# STLINK-V3EC.net
KiCad netlist of a schematic drawn in Altium Designer
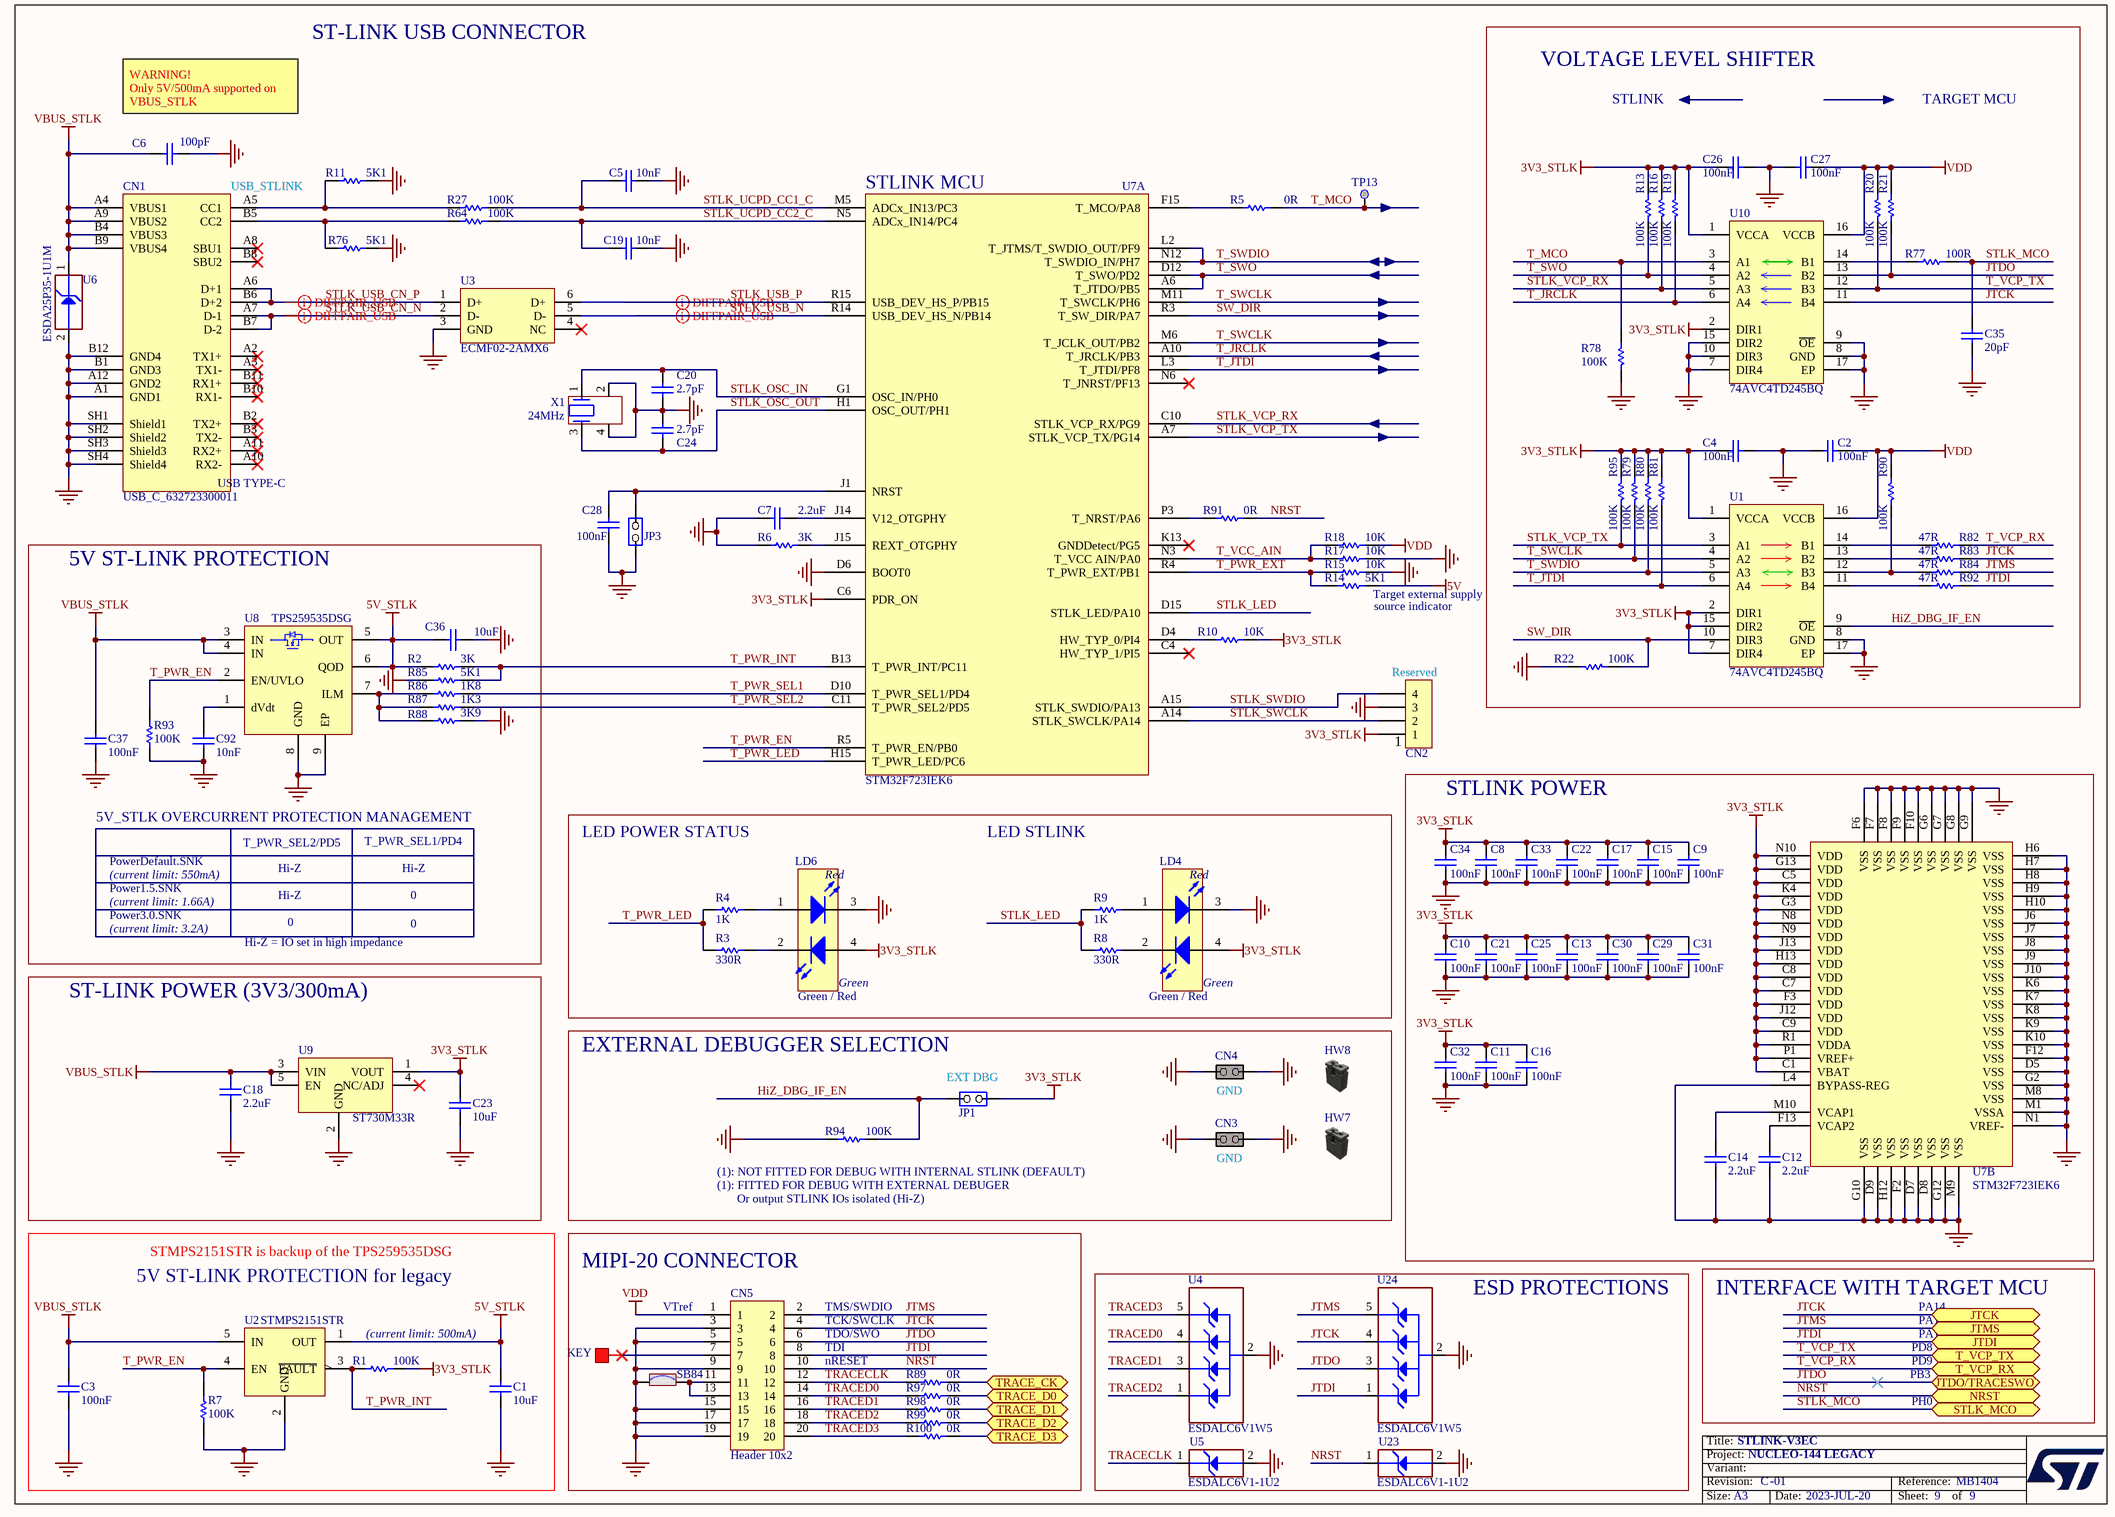
[diagram p0: STLINK-V3EC.SchDoc]

(export (version "E")
  (design (tool "Eeschema 10.0.6"))
  (components
    (comp (ref "C1")
      (value "10uF")
      (footprint "MCD_PARTS:C0603")
      (description "Capacitor, MLCC, 10uF, 10V, X5R, +/-10%, 0603, T=0.8mm")
      (fields (field (name "INTERNAL_PART_NUMBER") "MCD-00099") (field (name "MANUFACTURER") "MURATA"))
      (libsource (lib "MCD_PARTS_database") (part "Capacitor"))
    )
    (comp (ref "C2")
      (value "100nF")
      (footprint "MCD_PARTS:C0402")
      (description "Capacitor, MLCC, 100nF, 16V, X7R, 10%, 0402, T=0.5mm")
      (fields
        (field (name "INTERNAL_PART_NUMBER") "MCD-00006")
        (field (name "MANUFACTURER_PART_NUMBER") "CC0402KRX7R7BB104")
        (field (name "PROVIDED_BY") "SUBCO")
      )
      (libsource (lib "MCD_PARTS_database") (part "Capacitor"))
    )
    (comp (ref "C3")
      (value "100nF")
      (footprint "MCD_PARTS:C0402")
      (description "Capacitor, MLCC, 100nF, 25V, X7R, +/-10%, 0402, T=0.5mm")
      (fields (field (name "INTERNAL_PART_NUMBER") "MCD-02355") (field (name "MANUFACTURER") "WALSIN"))
      (libsource (lib "MCD_PARTS_database") (part "Capacitor"))
    )
    (comp (ref "C4")
      (value "100nF")
      (footprint "MCD_PARTS:C0402")
      (description "Capacitor, MLCC, 100nF, 16V, X7R, 10%, 0402, T=0.5mm")
      (fields
        (field (name "INTERNAL_PART_NUMBER") "MCD-00006")
        (field (name "MANUFACTURER_PART_NUMBER") "CC0402KRX7R7BB104")
        (field (name "PROVIDED_BY") "SUBCO")
      )
      (libsource (lib "MCD_PARTS_database") (part "Capacitor"))
    )
    (comp (ref "C5")
      (value "10nF")
      (footprint "MCD_PARTS:C0402")
      (description "Capacitor, MLCC, 10nF, 50V, X7R, +/-10%, 0402, T=0.5mm")
      (fields (field (name "INTERNAL_PART_NUMBER") "MCD-02198") (field (name "MANUFACTURER") "YAGEO"))
      (libsource (lib "MCD_PARTS_database") (part "Capacitor"))
    )
    (comp (ref "C6")
      (value "100pF")
      (footprint "MCD_PARTS:C0402")
      (description "Capacitor, MLCC, 100pF, 50V, NPO, +/-5%, 0402, T=0.5mm")
      (fields (field (name "INTERNAL_PART_NUMBER") "MCD-00205") (field (name "MANUFACTURER") "YAGEO"))
      (libsource (lib "MCD_PARTS_database") (part "Capacitor"))
    )
    (comp (ref "C7")
      (value "2.2uF")
      (footprint "MCD_PARTS:C0402")
      (description "Capacitor, MLCC, 2.2uF, 6.3V, X5R, +/-10%, 0402, T=0.5mm")
      (fields (field (name "INTERNAL_PART_NUMBER") "MCD-02606") (field (name "MANUFACTURER") "YAGEO"))
      (libsource (lib "MCD_PARTS_database") (part "Capacitor"))
    )
    (comp (ref "C8")
      (value "100nF")
      (footprint "MCD_PARTS:C0402")
      (description "Capacitor, MLCC, 100nF, 16V, X7R, 10%, 0402, T=0.5mm")
      (fields
        (field (name "INTERNAL_PART_NUMBER") "MCD-00006")
        (field (name "MANUFACTURER_PART_NUMBER") "CC0402KRX7R7BB104")
        (field (name "PROVIDED_BY") "SUBCO")
      )
      (libsource (lib "MCD_PARTS_database") (part "Capacitor"))
    )
    (comp (ref "C9")
      (value "100nF")
      (footprint "MCD_PARTS:C0402")
      (description "Capacitor, MLCC, 100nF, 16V, X7R, 10%, 0402, T=0.5mm")
      (fields
        (field (name "INTERNAL_PART_NUMBER") "MCD-00006")
        (field (name "MANUFACTURER_PART_NUMBER") "CC0402KRX7R7BB104")
        (field (name "PROVIDED_BY") "SUBCO")
      )
      (libsource (lib "MCD_PARTS_database") (part "Capacitor"))
    )
    (comp (ref "C10")
      (value "100nF")
      (footprint "MCD_PARTS:C0402")
      (description "Capacitor, MLCC, 100nF, 16V, X7R, 10%, 0402, T=0.5mm")
      (fields
        (field (name "INTERNAL_PART_NUMBER") "MCD-00006")
        (field (name "MANUFACTURER_PART_NUMBER") "CC0402KRX7R7BB104")
        (field (name "PROVIDED_BY") "SUBCO")
      )
      (libsource (lib "MCD_PARTS_database") (part "Capacitor"))
    )
    (comp (ref "C11")
      (value "100nF")
      (footprint "MCD_PARTS:C0402")
      (description "Capacitor, MLCC, 100nF, 16V, X7R, 10%, 0402, T=0.5mm")
      (fields
        (field (name "INTERNAL_PART_NUMBER") "MCD-00006")
        (field (name "MANUFACTURER_PART_NUMBER") "CC0402KRX7R7BB104")
        (field (name "PROVIDED_BY") "SUBCO")
      )
      (libsource (lib "MCD_PARTS_database") (part "Capacitor"))
    )
    (comp (ref "C12")
      (value "2.2uF")
      (footprint "MCD_PARTS:C0402")
      (description "Capacitor, MLCC, 2.2uF, 6.3V, X5R, +/-10%, 0402, T=0.5mm")
      (fields (field (name "INTERNAL_PART_NUMBER") "MCD-02606") (field (name "MANUFACTURER") "YAGEO"))
      (libsource (lib "MCD_PARTS_database") (part "Capacitor"))
    )
    (comp (ref "C13")
      (value "100nF")
      (footprint "MCD_PARTS:C0402")
      (description "Capacitor, MLCC, 100nF, 16V, X7R, 10%, 0402, T=0.5mm")
      (fields
        (field (name "INTERNAL_PART_NUMBER") "MCD-00006")
        (field (name "MANUFACTURER_PART_NUMBER") "CC0402KRX7R7BB104")
        (field (name "PROVIDED_BY") "SUBCO")
      )
      (libsource (lib "MCD_PARTS_database") (part "Capacitor"))
    )
    (comp (ref "C14")
      (value "2.2uF")
      (footprint "MCD_PARTS:C0402")
      (description "Capacitor, MLCC, 2.2uF, 6.3V, X5R, +/-10%, 0402, T=0.5mm")
      (fields (field (name "INTERNAL_PART_NUMBER") "MCD-02606") (field (name "MANUFACTURER") "YAGEO"))
      (libsource (lib "MCD_PARTS_database") (part "Capacitor"))
    )
    (comp (ref "C15")
      (value "100nF")
      (footprint "MCD_PARTS:C0402")
      (description "Capacitor, MLCC, 100nF, 16V, X7R, 10%, 0402, T=0.5mm")
      (fields
        (field (name "INTERNAL_PART_NUMBER") "MCD-00006")
        (field (name "MANUFACTURER_PART_NUMBER") "CC0402KRX7R7BB104")
        (field (name "PROVIDED_BY") "SUBCO")
      )
      (libsource (lib "MCD_PARTS_database") (part "Capacitor"))
    )
    (comp (ref "C16")
      (value "100nF")
      (footprint "MCD_PARTS:C0402")
      (description "Capacitor, MLCC, 100nF, 16V, X7R, 10%, 0402, T=0.5mm")
      (fields
        (field (name "INTERNAL_PART_NUMBER") "MCD-00006")
        (field (name "MANUFACTURER_PART_NUMBER") "CC0402KRX7R7BB104")
        (field (name "PROVIDED_BY") "SUBCO")
      )
      (libsource (lib "MCD_PARTS_database") (part "Capacitor"))
    )
    (comp (ref "C17")
      (value "100nF")
      (footprint "MCD_PARTS:C0402")
      (description "Capacitor, MLCC, 100nF, 16V, X7R, 10%, 0402, T=0.5mm")
      (fields
        (field (name "INTERNAL_PART_NUMBER") "MCD-00006")
        (field (name "MANUFACTURER_PART_NUMBER") "CC0402KRX7R7BB104")
        (field (name "PROVIDED_BY") "SUBCO")
      )
      (libsource (lib "MCD_PARTS_database") (part "Capacitor"))
    )
    (comp (ref "C18")
      (value "2.2uF")
      (footprint "MCD_PARTS:C0805")
      (description "Capacitor, MLCC, 2.2uF, 25V, X7R, +/-10%, 0805, T=1,25mm")
      (fields
        (field (name "INTERNAL_PART_NUMBER") "MCD-02372")
        (field (name "MANUFACTURER_PART_NUMBER") "GRM21BR71E225KE11L")
        (field (name "PROVIDED_BY") "SUBCO")
      )
      (libsource (lib "MCD_PARTS_database") (part "Capacitor"))
    )
    (comp (ref "C19")
      (value "10nF")
      (footprint "MCD_PARTS:C0402")
      (description "Capacitor, MLCC, 10nF, 50V, X7R, +/-10%, 0402, T=0.5mm")
      (fields (field (name "INTERNAL_PART_NUMBER") "MCD-02198") (field (name "MANUFACTURER") "YAGEO"))
      (libsource (lib "MCD_PARTS_database") (part "Capacitor"))
    )
    (comp (ref "C20")
      (value "2.7pF")
      (footprint "MCD_PARTS:C0402")
      (description "Capacitor, MLCC, 2.7pF, 50V, NPO, +/-0.1pF, 0402, T=0.5mm")
      (fields (field (name "INTERNAL_PART_NUMBER") "MCD-01774") (field (name "MANUFACTURER") "YAGEO"))
      (libsource (lib "MCD_PARTS_database") (part "Capacitor"))
    )
    (comp (ref "C21")
      (value "100nF")
      (footprint "MCD_PARTS:C0402")
      (description "Capacitor, MLCC, 100nF, 16V, X7R, 10%, 0402, T=0.5mm")
      (fields
        (field (name "INTERNAL_PART_NUMBER") "MCD-00006")
        (field (name "MANUFACTURER_PART_NUMBER") "CC0402KRX7R7BB104")
        (field (name "PROVIDED_BY") "SUBCO")
      )
      (libsource (lib "MCD_PARTS_database") (part "Capacitor"))
    )
    (comp (ref "C22")
      (value "100nF")
      (footprint "MCD_PARTS:C0402")
      (description "Capacitor, MLCC, 100nF, 16V, X7R, 10%, 0402, T=0.5mm")
      (fields
        (field (name "INTERNAL_PART_NUMBER") "MCD-00006")
        (field (name "MANUFACTURER_PART_NUMBER") "CC0402KRX7R7BB104")
        (field (name "PROVIDED_BY") "SUBCO")
      )
      (libsource (lib "MCD_PARTS_database") (part "Capacitor"))
    )
    (comp (ref "C23")
      (value "10uF")
      (footprint "MCD_PARTS:C0603")
      (description "Capacitor, MLCC, 10uF, 10V, X5R, +/-10%, 0603, T=0.8mm")
      (fields (field (name "INTERNAL_PART_NUMBER") "MCD-00099") (field (name "MANUFACTURER") "MURATA"))
      (libsource (lib "MCD_PARTS_database") (part "Capacitor"))
    )
    (comp (ref "C24")
      (value "2.7pF")
      (footprint "MCD_PARTS:C0402")
      (description "Capacitor, MLCC, 2.7pF, 50V, NPO, +/-0.1pF, 0402, T=0.5mm")
      (fields (field (name "INTERNAL_PART_NUMBER") "MCD-01774") (field (name "MANUFACTURER") "YAGEO"))
      (libsource (lib "MCD_PARTS_database") (part "Capacitor"))
    )
    (comp (ref "C25")
      (value "100nF")
      (footprint "MCD_PARTS:C0402")
      (description "Capacitor, MLCC, 100nF, 16V, X7R, 10%, 0402, T=0.5mm")
      (fields
        (field (name "INTERNAL_PART_NUMBER") "MCD-00006")
        (field (name "MANUFACTURER_PART_NUMBER") "CC0402KRX7R7BB104")
        (field (name "PROVIDED_BY") "SUBCO")
      )
      (libsource (lib "MCD_PARTS_database") (part "Capacitor"))
    )
    (comp (ref "C26")
      (value "100nF")
      (footprint "MCD_PARTS:C0402")
      (description "Capacitor, MLCC, 100nF, 16V, X7R, 10%, 0402, T=0.5mm")
      (fields
        (field (name "INTERNAL_PART_NUMBER") "MCD-00006")
        (field (name "MANUFACTURER_PART_NUMBER") "CC0402KRX7R7BB104")
        (field (name "PROVIDED_BY") "SUBCO")
      )
      (libsource (lib "MCD_PARTS_database") (part "Capacitor"))
    )
    (comp (ref "C27")
      (value "100nF")
      (footprint "MCD_PARTS:C0402")
      (description "Capacitor, MLCC, 100nF, 16V, X7R, 10%, 0402, T=0.5mm")
      (fields
        (field (name "INTERNAL_PART_NUMBER") "MCD-00006")
        (field (name "MANUFACTURER_PART_NUMBER") "CC0402KRX7R7BB104")
        (field (name "PROVIDED_BY") "SUBCO")
      )
      (libsource (lib "MCD_PARTS_database") (part "Capacitor"))
    )
    (comp (ref "C28")
      (value "100nF")
      (footprint "MCD_PARTS:C0402")
      (description "Capacitor, MLCC, 100nF, 16V, X7R, 10%, 0402, T=0.5mm")
      (fields
        (field (name "INTERNAL_PART_NUMBER") "MCD-00006")
        (field (name "MANUFACTURER_PART_NUMBER") "CC0402KRX7R7BB104")
        (field (name "PROVIDED_BY") "SUBCO")
      )
      (libsource (lib "MCD_PARTS_database") (part "Capacitor"))
    )
    (comp (ref "C29")
      (value "100nF")
      (footprint "MCD_PARTS:C0402")
      (description "Capacitor, MLCC, 100nF, 16V, X7R, 10%, 0402, T=0.5mm")
      (fields
        (field (name "INTERNAL_PART_NUMBER") "MCD-00006")
        (field (name "MANUFACTURER_PART_NUMBER") "CC0402KRX7R7BB104")
        (field (name "PROVIDED_BY") "SUBCO")
      )
      (libsource (lib "MCD_PARTS_database") (part "Capacitor"))
    )
    (comp (ref "C30")
      (value "100nF")
      (footprint "MCD_PARTS:C0402")
      (description "Capacitor, MLCC, 100nF, 16V, X7R, 10%, 0402, T=0.5mm")
      (fields
        (field (name "INTERNAL_PART_NUMBER") "MCD-00006")
        (field (name "MANUFACTURER_PART_NUMBER") "CC0402KRX7R7BB104")
        (field (name "PROVIDED_BY") "SUBCO")
      )
      (libsource (lib "MCD_PARTS_database") (part "Capacitor"))
    )
    (comp (ref "C31")
      (value "100nF")
      (footprint "MCD_PARTS:C0402")
      (description "Capacitor, MLCC, 100nF, 16V, X7R, 10%, 0402, T=0.5mm")
      (fields
        (field (name "INTERNAL_PART_NUMBER") "MCD-00006")
        (field (name "MANUFACTURER_PART_NUMBER") "CC0402KRX7R7BB104")
        (field (name "PROVIDED_BY") "SUBCO")
      )
      (libsource (lib "MCD_PARTS_database") (part "Capacitor"))
    )
    (comp (ref "C32")
      (value "100nF")
      (footprint "MCD_PARTS:C0402")
      (description "Capacitor, MLCC, 100nF, 16V, X7R, 10%, 0402, T=0.5mm")
      (fields
        (field (name "INTERNAL_PART_NUMBER") "MCD-00006")
        (field (name "MANUFACTURER_PART_NUMBER") "CC0402KRX7R7BB104")
        (field (name "PROVIDED_BY") "SUBCO")
      )
      (libsource (lib "MCD_PARTS_database") (part "Capacitor"))
    )
    (comp (ref "C33")
      (value "100nF")
      (footprint "MCD_PARTS:C0402")
      (description "Capacitor, MLCC, 100nF, 16V, X7R, 10%, 0402, T=0.5mm")
      (fields
        (field (name "INTERNAL_PART_NUMBER") "MCD-00006")
        (field (name "MANUFACTURER_PART_NUMBER") "CC0402KRX7R7BB104")
        (field (name "PROVIDED_BY") "SUBCO")
      )
      (libsource (lib "MCD_PARTS_database") (part "Capacitor"))
    )
    (comp (ref "C34")
      (value "100nF")
      (footprint "MCD_PARTS:C0402")
      (description "Capacitor, MLCC, 100nF, 16V, X7R, 10%, 0402, T=0.5mm")
      (fields
        (field (name "INTERNAL_PART_NUMBER") "MCD-00006")
        (field (name "MANUFACTURER_PART_NUMBER") "CC0402KRX7R7BB104")
        (field (name "PROVIDED_BY") "SUBCO")
      )
      (libsource (lib "MCD_PARTS_database") (part "Capacitor"))
    )
    (comp (ref "C35")
      (value "20pF")
      (footprint "MCD_PARTS:C0402")
      (description "Capacitor, MLCC, 20pF, 50V, NPO, 5%, 0402, T=0,5mm")
      (fields
        (field (name "INTERNAL_PART_NUMBER") "MCD-00016")
        (field (name "MANUFACTURER_PART_NUMBER") "CC0402JRNPO9BN200")
        (field (name "PROVIDED_BY") "SUBCO")
      )
      (libsource (lib "MCD_PARTS_database") (part "Capacitor"))
    )
    (comp (ref "C36")
      (value "10uF")
      (footprint "MCD_PARTS:C0603")
      (description "Capacitor, MLCC, 10uF, 10V, X5R, +/-10%, 0603, T=0.8mm")
      (fields (field (name "INTERNAL_PART_NUMBER") "MCD-00099") (field (name "MANUFACTURER") "MURATA"))
      (libsource (lib "MCD_PARTS_database") (part "Capacitor"))
    )
    (comp (ref "C37")
      (value "100nF")
      (footprint "MCD_PARTS:C0402")
      (description "Capacitor, MLCC, 100nF, 25V, X7R, +/-10%, 0402, T=0.5mm")
      (fields (field (name "INTERNAL_PART_NUMBER") "MCD-02355") (field (name "MANUFACTURER") "WALSIN"))
      (libsource (lib "MCD_PARTS_database") (part "Capacitor"))
    )
    (comp (ref "C92")
      (value "10nF")
      (footprint "MCD_PARTS:C0402")
      (description "Capacitor, MLCC, 10nF, 50V, X7R, +/-10%, 0402, T=0.5mm")
      (fields (field (name "INTERNAL_PART_NUMBER") "MCD-02198") (field (name "MANUFACTURER") "YAGEO"))
      (libsource (lib "MCD_PARTS_database") (part "Capacitor"))
    )
    (comp (ref "CN1")
      (value "USB_C_632723300011")
      (footprint "MCD_PARTS:CON_USB-TYPEC_WE_632723300011")
      (description "Connector_USB_TypeC, 24pins, RA, TH, T=1.9mm (USB certified)")
      (fields
        (field (name "INTERNAL_PART_NUMBER") "MCD-02273")
        (field (name "MANUFACTURER") "WURTH ELEKTRONIK")
      )
      (libsource (lib "MCD_PARTS_database") (part "USB_TYPE_C_Receptacle"))
    )
    (comp (ref "CN2")
      (value "Header 4x1")
      (footprint "MCD_PARTS:CON_SAMTEC_TSW-104-07-G-S")
      (description "Header, 4x1, 2,54mm, VR, TH, Height 5.84mm/2.54mm")
      (fields
        (field (name "INTERNAL_PART_NUMBER") "MCD-00029")
        (field (name "MANUFACTURER_PART_NUMBER") "TSW-104-07-x-S")
        (field (name "PROVIDED_BY") "SUBCO")
      )
      (libsource (lib "MCD_PARTS_database") (part "Header 4x1"))
    )
    (comp (ref "CN3")
      (value "Jumper_Header 2x1")
      (footprint "MCD_PARTS:CON_SAMTEC_TSW-102-09-X-S")
      (description "Header, 2x1, 2,54mm, VR, TH, Height 5.84mm/10.16mm")
      (fields
        (field (name "INTERNAL_PART_NUMBER") "MCD-00214")
        (field (name "MANUFACTURER_PART_NUMBER") "TSW-102-09-x-S")
        (field (name "PROVIDED_BY") "SUBCO")
      )
      (libsource (lib "MCD_PARTS_database") (part "Jumper_Header 2x1"))
    )
    (comp (ref "CN4")
      (value "Jumper_Header 2x1")
      (footprint "MCD_PARTS:CON_SAMTEC_TSW-102-09-X-S")
      (description "Header, 2x1, 2,54mm, VR, TH, Height 5.84mm/10.16mm")
      (fields
        (field (name "INTERNAL_PART_NUMBER") "MCD-00214")
        (field (name "MANUFACTURER_PART_NUMBER") "TSW-102-09-x-S")
        (field (name "PROVIDED_BY") "SUBCO")
      )
      (libsource (lib "MCD_PARTS_database") (part "Jumper_Header 2x1"))
    )
    (comp (ref "CN5")
      (value "Header 10x2")
      (footprint "MCD_PARTS:CON_SAMTEC_FTSH-110-01-L-DV")
      (description "Header, 10x2, 1.27mm, VR, SMD, T=3.05mm")
      (fields (field (name "INTERNAL_PART_NUMBER") "MCD-00557") (field (name "BMS_PART_NUMBER") "9183690"))
      (libsource (lib "MCD_PARTS_database") (part "Header 10x2"))
    )
    (comp (ref "HW7")
      (value "Shunt Black 2.54mm")
      (description "SHUNT 2.54mm BLACK")
      (fields
        (field (name "INTERNAL_PART_NUMBER") "MCD-00043")
        (field (name "MANUFACTURER_PART_NUMBER") "SNT-100-BK-G")
        (field (name "PROVIDED_BY") "SUBCO")
      )
      (libsource (lib "MCD_PARTS_database") (part "Shunt Black 2.54mm"))
    )
    (comp (ref "HW8")
      (value "Shunt Black 2.54mm")
      (description "SHUNT 2.54mm BLACK")
      (fields
        (field (name "INTERNAL_PART_NUMBER") "MCD-00043")
        (field (name "MANUFACTURER_PART_NUMBER") "SNT-100-BK-G")
        (field (name "PROVIDED_BY") "SUBCO")
      )
      (libsource (lib "MCD_PARTS_database") (part "Shunt Black 2.54mm"))
    )
    (comp (ref "JP1")
      (value "Jumper_Header 2x1")
      (footprint "MCD_PARTS:CON_SAMTEC_TSW-102-07-G-S")
      (description "Header, 2x1, 2,54mm, VR, TH, Height 5.84mm/2.54mm")
      (fields (field (name "INTERNAL_PART_NUMBER") "MCD-00045") (field (name "MANUFACTURER") "SAMTEC"))
      (libsource (lib "MCD_PARTS_database") (part "Jumper_Header 2x1"))
    )
    (comp (ref "JP3")
      (value "Jumper_Header 2x1")
      (footprint "MCD_PARTS:CON_SAMTEC_TSW-102-07-G-S")
      (description "Header, 2x1, 2,54mm, VR, TH, Height 5.84mm/2.54mm")
      (fields (field (name "INTERNAL_PART_NUMBER") "MCD-00045") (field (name "MANUFACTURER") "SAMTEC"))
      (libsource (lib "MCD_PARTS_database") (part "Jumper_Header 2x1"))
    )
    (comp (ref "LD4")
      (value "Green / Red")
      (footprint "MCD_PARTS:LED_BI-GR_WE-150141SV73110")
      (description "LED Bicolor, Green/Red, 2V, 20mA,  4-PLCC")
      (fields
        (field (name "INTERNAL_PART_NUMBER") "MCD-02631")
        (field (name "MANUFACTURER") "WURTH ELEKTRONIK")
      )
      (libsource (lib "MCD_PARTS_database") (part "LED_BICOLOR"))
    )
    (comp (ref "LD6")
      (value "Green / Red")
      (footprint "MCD_PARTS:LED_BI-GR_WE-150141SV73110")
      (description "LED Bicolor, Green/Red, 2V, 20mA,  4-PLCC")
      (fields
        (field (name "INTERNAL_PART_NUMBER") "MCD-02631")
        (field (name "MANUFACTURER") "WURTH ELEKTRONIK")
      )
      (libsource (lib "MCD_PARTS_database") (part "LED_BICOLOR"))
    )
    (comp (ref "R1")
      (value "100K")
      (footprint "MCD_PARTS:R0402")
      (description "Resistor,100K,0402,1%,1/16W")
      (fields
        (field (name "INTERNAL_PART_NUMBER") "MCD-00059")
        (field (name "MANUFACTURER_PART_NUMBER") "RC0402FR-07100KL")
        (field (name "PROVIDED_BY") "SUBCO")
      )
      (libsource (lib "MCD_PARTS_database") (part "Resistor"))
    )
    (comp (ref "R2")
      (value "3K")
      (footprint "MCD_PARTS:R0402")
      (description "Resistor, 3K, 0402, +/-1%, 1/16W")
      (fields (field (name "INTERNAL_PART_NUMBER") "MCD-00185") (field (name "MANUFACTURER") "YAGEO"))
      (libsource (lib "MCD_PARTS_database") (part "Resistor"))
    )
    (comp (ref "R3")
      (value "330R")
      (footprint "MCD_PARTS:R0402")
      (description "Resistor, 330R, 0402, +/-1%, 1/16W")
      (fields (field (name "INTERNAL_PART_NUMBER") "MCD-00062") (field (name "MANUFACTURER") "YAGEO"))
      (libsource (lib "MCD_PARTS_database") (part "Resistor"))
    )
    (comp (ref "R4")
      (value "1K")
      (footprint "MCD_PARTS:R0402")
      (description "Resistor, 1K, 0402, +/-0.1%, 1/16W, +/-25ppm/°C")
      (fields (field (name "INTERNAL_PART_NUMBER") "MCD-02665") (field (name "MANUFACTURER") "YAGEO"))
      (libsource (lib "MCD_PARTS_database") (part "Resistor"))
    )
    (comp (ref "R5")
      (value "0R")
      (footprint "MCD_PARTS:R0402")
      (description "Resistor, 0R, 0402, +/-5%, 1/16W")
      (fields (field (name "INTERNAL_PART_NUMBER") "MCD-00052") (field (name "MANUFACTURER") "YAGEO"))
      (libsource (lib "MCD_PARTS_database") (part "Resistor"))
    )
    (comp (ref "R6")
      (value "3K")
      (footprint "MCD_PARTS:R0402")
      (description "Resistor,3K,0402,1%,1/16W")
      (fields
        (field (name "INTERNAL_PART_NUMBER") "MCD-00185")
        (field (name "MANUFACTURER_PART_NUMBER") "RC0402FR-073KL")
        (field (name "PROVIDED_BY") "SUBCO")
      )
      (libsource (lib "MCD_PARTS_database") (part "Resistor"))
    )
    (comp (ref "R7")
      (value "100K")
      (footprint "MCD_PARTS:R0402")
      (description "Resistor,100K,0402,1%,1/16W")
      (fields
        (field (name "INTERNAL_PART_NUMBER") "MCD-00059")
        (field (name "MANUFACTURER_PART_NUMBER") "RC0402FR-07100KL")
        (field (name "PROVIDED_BY") "SUBCO")
      )
      (libsource (lib "MCD_PARTS_database") (part "Resistor"))
    )
    (comp (ref "R8")
      (value "330R")
      (footprint "MCD_PARTS:R0402")
      (description "Resistor, 330R, 0402, +/-1%, 1/16W")
      (fields (field (name "INTERNAL_PART_NUMBER") "MCD-00062") (field (name "MANUFACTURER") "YAGEO"))
      (libsource (lib "MCD_PARTS_database") (part "Resistor"))
    )
    (comp (ref "R9")
      (value "1K")
      (footprint "MCD_PARTS:R0402")
      (description "Resistor, 1K, 0402, +/-0.1%, 1/16W, +/-25ppm/°C")
      (fields (field (name "INTERNAL_PART_NUMBER") "MCD-02665") (field (name "MANUFACTURER") "YAGEO"))
      (libsource (lib "MCD_PARTS_database") (part "Resistor"))
    )
    (comp (ref "R10")
      (value "10K")
      (footprint "MCD_PARTS:R0402")
      (description "Resistor,10K,0402,1%,1/16W")
      (fields
        (field (name "INTERNAL_PART_NUMBER") "MCD-00053")
        (field (name "MANUFACTURER_PART_NUMBER") "RC0402FR-0710KL")
        (field (name "PROVIDED_BY") "SUBCO")
      )
      (libsource (lib "MCD_PARTS_database") (part "Resistor"))
    )
    (comp (ref "R11")
      (value "5K1")
      (footprint "MCD_PARTS:R0402")
      (description "Resistor, 5K1, 0402, +/-1%, 1/16W")
      (fields (field (name "INTERNAL_PART_NUMBER") "MCD-00333") (field (name "MANUFACTURER") "YAGEO"))
      (libsource (lib "MCD_PARTS_database") (part "Resistor"))
    )
    (comp (ref "R13")
      (value "100K")
      (footprint "MCD_PARTS:R0402")
      (description "Resistor,100K,0402,1%,1/16W")
      (fields
        (field (name "INTERNAL_PART_NUMBER") "MCD-00059")
        (field (name "MANUFACTURER_PART_NUMBER") "RC0402FR-07100KL")
        (field (name "PROVIDED_BY") "Subcon")
      )
      (libsource (lib "MCD_PARTS_database") (part "Resistor"))
    )
    (comp (ref "R14")
      (value "5K1")
      (footprint "MCD_PARTS:R0402")
      (description "Resistor, 5K1, 0402, +/-1%, 1/16W")
      (fields (field (name "INTERNAL_PART_NUMBER") "MCD-00333") (field (name "MANUFACTURER") "YAGEO"))
      (libsource (lib "MCD_PARTS_database") (part "Resistor"))
    )
    (comp (ref "R15")
      (value "10K")
      (footprint "MCD_PARTS:R0402")
      (description "Resistor, 10K, 0402, +/-1%, 1/16W")
      (fields (field (name "INTERNAL_PART_NUMBER") "MCD-00053") (field (name "BMS_PART_NUMBER") "9131590"))
      (libsource (lib "MCD_PARTS_database") (part "Resistor"))
    )
    (comp (ref "R16")
      (value "100K")
      (footprint "MCD_PARTS:R0402")
      (description "Resistor,100K,0402,1%,1/16W")
      (fields
        (field (name "INTERNAL_PART_NUMBER") "MCD-00059")
        (field (name "MANUFACTURER_PART_NUMBER") "RC0402FR-07100KL")
        (field (name "PROVIDED_BY") "Subcon")
      )
      (libsource (lib "MCD_PARTS_database") (part "Resistor"))
    )
    (comp (ref "R17")
      (value "10K")
      (footprint "MCD_PARTS:R0402")
      (description "Resistor, 10K, 0402, +/-1%, 1/16W")
      (fields (field (name "INTERNAL_PART_NUMBER") "MCD-00053") (field (name "BMS_PART_NUMBER") "9131590"))
      (libsource (lib "MCD_PARTS_database") (part "Resistor"))
    )
    (comp (ref "R18")
      (value "10K")
      (footprint "MCD_PARTS:R0402")
      (description "Resistor, 10K, 0402, +/-1%, 1/16W")
      (fields (field (name "INTERNAL_PART_NUMBER") "MCD-00053") (field (name "BMS_PART_NUMBER") "9131590"))
      (libsource (lib "MCD_PARTS_database") (part "Resistor"))
    )
    (comp (ref "R19")
      (value "100K")
      (footprint "MCD_PARTS:R0402")
      (description "Resistor,100K,0402,1%,1/16W")
      (fields
        (field (name "INTERNAL_PART_NUMBER") "MCD-00059")
        (field (name "MANUFACTURER_PART_NUMBER") "RC0402FR-07100KL")
        (field (name "PROVIDED_BY") "Subcon")
      )
      (libsource (lib "MCD_PARTS_database") (part "Resistor"))
    )
    (comp (ref "R20")
      (value "100K")
      (footprint "MCD_PARTS:R0402")
      (description "Resistor,100K,0402,1%,1/16W")
      (fields
        (field (name "INTERNAL_PART_NUMBER") "MCD-00059")
        (field (name "MANUFACTURER_PART_NUMBER") "RC0402FR-07100KL")
        (field (name "PROVIDED_BY") "Subcon")
      )
      (libsource (lib "MCD_PARTS_database") (part "Resistor"))
    )
    (comp (ref "R21")
      (value "100K")
      (footprint "MCD_PARTS:R0402")
      (description "Resistor,100K,0402,1%,1/16W")
      (fields
        (field (name "INTERNAL_PART_NUMBER") "MCD-00059")
        (field (name "MANUFACTURER_PART_NUMBER") "RC0402FR-07100KL")
        (field (name "PROVIDED_BY") "Subcon")
      )
      (libsource (lib "MCD_PARTS_database") (part "Resistor"))
    )
    (comp (ref "R22")
      (value "100K")
      (footprint "MCD_PARTS:R0402")
      (description "Resistor,100K,0402,1%,1/16W")
      (fields
        (field (name "INTERNAL_PART_NUMBER") "MCD-00059")
        (field (name "MANUFACTURER_PART_NUMBER") "RC0402FR-07100KL")
        (field (name "PROVIDED_BY") "Subcon")
      )
      (libsource (lib "MCD_PARTS_database") (part "Resistor"))
    )
    (comp (ref "R27")
      (value "100K")
      (footprint "MCD_PARTS:R0402")
      (description "Resistor, 100K, 0402, +/-1%, 1/16W")
      (fields (field (name "INTERNAL_PART_NUMBER") "MCD-00059") (field (name "MANUFACTURER") "YAGEO"))
      (libsource (lib "MCD_PARTS_database") (part "Resistor"))
    )
    (comp (ref "R64")
      (value "100K")
      (footprint "MCD_PARTS:R0402")
      (description "Resistor, 100K, 0402, +/-1%, 1/16W")
      (fields (field (name "INTERNAL_PART_NUMBER") "MCD-00059") (field (name "MANUFACTURER") "YAGEO"))
      (libsource (lib "MCD_PARTS_database") (part "Resistor"))
    )
    (comp (ref "R76")
      (value "5K1")
      (footprint "MCD_PARTS:R0402")
      (description "Resistor, 5K1, 0402, +/-1%, 1/16W")
      (fields (field (name "INTERNAL_PART_NUMBER") "MCD-00333") (field (name "MANUFACTURER") "YAGEO"))
      (libsource (lib "MCD_PARTS_database") (part "Resistor"))
    )
    (comp (ref "R77")
      (value "100R")
      (footprint "MCD_PARTS:R0402")
      (description "Resistor, 100R, 0402, +/- 1%, 1/16W")
      (fields (field (name "INTERNAL_PART_NUMBER") "MCD-00067") (field (name "MANUFACTURER") "YAGEO"))
      (libsource (lib "MCD_PARTS_database") (part "Resistor"))
    )
    (comp (ref "R78")
      (value "100K")
      (footprint "MCD_PARTS:R0402")
      (description "Resistor,100K,0402,1%,1/16W")
      (fields
        (field (name "INTERNAL_PART_NUMBER") "MCD-00059")
        (field (name "MANUFACTURER_PART_NUMBER") "RC0402FR-07100KL")
        (field (name "PROVIDED_BY") "Subcon")
      )
      (libsource (lib "MCD_PARTS_database") (part "Resistor"))
    )
    (comp (ref "R79")
      (value "100K")
      (footprint "MCD_PARTS:R0402")
      (description "Resistor,100K,0402,1%,1/16W")
      (fields
        (field (name "INTERNAL_PART_NUMBER") "MCD-00059")
        (field (name "MANUFACTURER_PART_NUMBER") "RC0402FR-07100KL")
        (field (name "PROVIDED_BY") "Subcon")
      )
      (libsource (lib "MCD_PARTS_database") (part "Resistor"))
    )
    (comp (ref "R80")
      (value "100K")
      (footprint "MCD_PARTS:R0402")
      (description "Resistor,100K,0402,1%,1/16W")
      (fields
        (field (name "INTERNAL_PART_NUMBER") "MCD-00059")
        (field (name "MANUFACTURER_PART_NUMBER") "RC0402FR-07100KL")
        (field (name "PROVIDED_BY") "Subcon")
      )
      (libsource (lib "MCD_PARTS_database") (part "Resistor"))
    )
    (comp (ref "R81")
      (value "100K")
      (footprint "MCD_PARTS:R0402")
      (description "Resistor,100K,0402,1%,1/16W")
      (fields
        (field (name "INTERNAL_PART_NUMBER") "MCD-00059")
        (field (name "MANUFACTURER_PART_NUMBER") "RC0402FR-07100KL")
        (field (name "PROVIDED_BY") "Subcon")
      )
      (libsource (lib "MCD_PARTS_database") (part "Resistor"))
    )
    (comp (ref "R82")
      (value "47R")
      (footprint "MCD_PARTS:R0402")
      (description "Resistor,47R,0402,1%,1/16W")
      (fields
        (field (name "INTERNAL_PART_NUMBER") "MCD-00481")
        (field (name "MANUFACTURER_PART_NUMBER") "RC0402FR-0747RL")
        (field (name "PROVIDED_BY") "SUBCO")
      )
      (libsource (lib "MCD_PARTS_database") (part "Resistor"))
    )
    (comp (ref "R83")
      (value "47R")
      (footprint "MCD_PARTS:R0402")
      (description "Resistor,47R,0402,1%,1/16W")
      (fields
        (field (name "INTERNAL_PART_NUMBER") "MCD-00481")
        (field (name "MANUFACTURER_PART_NUMBER") "RC0402FR-0747RL")
        (field (name "PROVIDED_BY") "SUBCO")
      )
      (libsource (lib "MCD_PARTS_database") (part "Resistor"))
    )
    (comp (ref "R84")
      (value "47R")
      (footprint "MCD_PARTS:R0402")
      (description "Resistor,47R,0402,1%,1/16W")
      (fields
        (field (name "INTERNAL_PART_NUMBER") "MCD-00481")
        (field (name "MANUFACTURER_PART_NUMBER") "RC0402FR-0747RL")
        (field (name "PROVIDED_BY") "SUBCO")
      )
      (libsource (lib "MCD_PARTS_database") (part "Resistor"))
    )
    (comp (ref "R85")
      (value "5K1")
      (footprint "MCD_PARTS:R0402")
      (description "Resistor, 5K1, 0402, +/-1%, 1/16W")
      (fields (field (name "INTERNAL_PART_NUMBER") "MCD-00333") (field (name "MANUFACTURER") "YAGEO"))
      (libsource (lib "MCD_PARTS_database") (part "Resistor"))
    )
    (comp (ref "R86")
      (value "1K8")
      (footprint "MCD_PARTS:R0402")
      (description "Resistor, 1K8, 0402, +/-1%, 1/16W")
      (fields (field (name "INTERNAL_PART_NUMBER") "MCD-00409") (field (name "MANUFACTURER") "YAGEO"))
      (libsource (lib "MCD_PARTS_database") (part "Resistor"))
    )
    (comp (ref "R87")
      (value "1K3")
      (footprint "MCD_PARTS:R0402")
      (description "Resistor, 1K3, 0402, +/-1%, 1/16W")
      (fields (field (name "INTERNAL_PART_NUMBER") "MCD-00381") (field (name "MANUFACTURER") "YAGEO"))
      (libsource (lib "MCD_PARTS_database") (part "Resistor"))
    )
    (comp (ref "R88")
      (value "3K9")
      (footprint "MCD_PARTS:R0402")
      (description "Resistor, 3K9, 0402, +/-1%, 1/16W, +/-100ppm/°C")
      (fields (field (name "INTERNAL_PART_NUMBER") "MCD-02455") (field (name "MANUFACTURER") "YAGEO"))
      (libsource (lib "MCD_PARTS_database") (part "Resistor"))
    )
    (comp (ref "R89")
      (value "0R")
      (footprint "MCD_PARTS:R0402")
      (description "Resistor,0R,0402,5%,1/16W")
      (fields
        (field (name "INTERNAL_PART_NUMBER") "MCD-00052")
        (field (name "MANUFACTURER_PART_NUMBER") "RC0402JR-070RL")
        (field (name "PROVIDED_BY") "SUBCO")
      )
      (libsource (lib "MCD_PARTS_database") (part "Resistor"))
    )
    (comp (ref "R90")
      (value "100K")
      (footprint "MCD_PARTS:R0402")
      (description "Resistor,100K,0402,1%,1/16W")
      (fields
        (field (name "INTERNAL_PART_NUMBER") "MCD-00059")
        (field (name "MANUFACTURER_PART_NUMBER") "RC0402FR-07100KL")
        (field (name "PROVIDED_BY") "Subcon")
      )
      (libsource (lib "MCD_PARTS_database") (part "Resistor"))
    )
    (comp (ref "R91")
      (value "0R")
      (footprint "MCD_PARTS:R0402")
      (description "Resistor, 0R, 0402, +/-5%, 1/16W")
      (fields (field (name "INTERNAL_PART_NUMBER") "MCD-00052") (field (name "MANUFACTURER") "YAGEO"))
      (libsource (lib "MCD_PARTS_database") (part "Resistor"))
    )
    (comp (ref "R92")
      (value "47R")
      (footprint "MCD_PARTS:R0402")
      (description "Resistor,47R,0402,1%,1/16W")
      (fields
        (field (name "INTERNAL_PART_NUMBER") "MCD-00481")
        (field (name "MANUFACTURER_PART_NUMBER") "RC0402FR-0747RL")
        (field (name "PROVIDED_BY") "SUBCO")
      )
      (libsource (lib "MCD_PARTS_database") (part "Resistor"))
    )
    (comp (ref "R93")
      (value "100K")
      (footprint "MCD_PARTS:R0402")
      (description "Resistor, 100K, 0402, +/-1%, 1/16W")
      (fields (field (name "INTERNAL_PART_NUMBER") "MCD-00059") (field (name "MANUFACTURER") "YAGEO"))
      (libsource (lib "MCD_PARTS_database") (part "Resistor"))
    )
    (comp (ref "R94")
      (value "100K")
      (footprint "MCD_PARTS:R0402")
      (description "Resistor, 100K, 0402, +/-1%, 1/16W")
      (fields (field (name "INTERNAL_PART_NUMBER") "MCD-00059") (field (name "MANUFACTURER") "YAGEO"))
      (libsource (lib "MCD_PARTS_database") (part "Resistor"))
    )
    (comp (ref "R95")
      (value "100K")
      (footprint "MCD_PARTS:R0402")
      (description "Resistor,100K,0402,1%,1/16W")
      (fields
        (field (name "INTERNAL_PART_NUMBER") "MCD-00059")
        (field (name "MANUFACTURER_PART_NUMBER") "RC0402FR-07100KL")
        (field (name "PROVIDED_BY") "Subcon")
      )
      (libsource (lib "MCD_PARTS_database") (part "Resistor"))
    )
    (comp (ref "R97")
      (value "0R")
      (footprint "MCD_PARTS:R0402")
      (description "Resistor,0R,0402,5%,1/16W")
      (fields
        (field (name "INTERNAL_PART_NUMBER") "MCD-00052")
        (field (name "MANUFACTURER_PART_NUMBER") "RC0402JR-070RL")
        (field (name "PROVIDED_BY") "SUBCO")
      )
      (libsource (lib "MCD_PARTS_database") (part "Resistor"))
    )
    (comp (ref "R98")
      (value "0R")
      (footprint "MCD_PARTS:R0402")
      (description "Resistor,0R,0402,5%,1/16W")
      (fields
        (field (name "INTERNAL_PART_NUMBER") "MCD-00052")
        (field (name "MANUFACTURER_PART_NUMBER") "RC0402JR-070RL")
        (field (name "PROVIDED_BY") "SUBCO")
      )
      (libsource (lib "MCD_PARTS_database") (part "Resistor"))
    )
    (comp (ref "R99")
      (value "0R")
      (footprint "MCD_PARTS:R0402")
      (description "Resistor,0R,0402,5%,1/16W")
      (fields
        (field (name "INTERNAL_PART_NUMBER") "MCD-00052")
        (field (name "MANUFACTURER_PART_NUMBER") "RC0402JR-070RL")
        (field (name "PROVIDED_BY") "SUBCO")
      )
      (libsource (lib "MCD_PARTS_database") (part "Resistor"))
    )
    (comp (ref "R100")
      (value "0R")
      (footprint "MCD_PARTS:R0402")
      (description "Resistor,0R,0402,5%,1/16W")
      (fields
        (field (name "INTERNAL_PART_NUMBER") "MCD-00052")
        (field (name "MANUFACTURER_PART_NUMBER") "RC0402JR-070RL")
        (field (name "PROVIDED_BY") "SUBCO")
      )
      (libsource (lib "MCD_PARTS_database") (part "Resistor"))
    )
    (comp (ref "SB84")
      (value "SB_ON")
      (footprint "MCD_PARTS:SOLDER-BRIDGE_R0402-0R")
      (description "Solder Bridge 0402 ON")
      (fields
        (field (name "INTERNAL_PART_NUMBER") "MCD-01618")
        (field (name "MANUFACTURER_PART_NUMBER") "RC0402JR-070RL")
        (field (name "PROVIDED_BY") "SUBCO")
      )
      (libsource (lib "MCD_PARTS_database") (part "SB_ON"))
    )
    (comp (ref "TP13")
      (value "Test Point")
      (footprint "MCD_PARTS:TP_SMD_1MM")
      (description "Test Point 1mm")
      (fields
        (field (name "INTERNAL_PART_NUMBER") "MCD-00074")
        (field (name "MANUFACTURER_PART_NUMBER") "n/a")
      )
      (libsource (lib "MCD_PARTS_database") (part "Test Point"))
    )
    (comp (ref "U1")
      (value "74AVC4TD245BQ")
      (footprint "MCD_PARTS:ICC_DHVQFN16-EPAD_SOT763-1_2P5X3P5_H0P85_P050")
      (description "4-bit dual supply translating transceiver with configurable voltage translation; 3-state")
      (fields
        (field (name "INTERNAL_PART_NUMBER") "MCD-01945")
        (field (name "MANUFACTURER_PART_NUMBER") "74AVC4TD245BQ,115")
      )
      (libsource (lib "MCD_PARTS_database") (part "74AVC4TD245BQ"))
    )
    (comp (ref "U2")
      (value "STMPS2151STR")
      (footprint "MCD_PARTS:MOS_SOT23-5L")
      (description "500mA, Enhanced single channel power switches with active high enable pin")
      (fields
        (field (name "INTERNAL_PART_NUMBER") "MCD-00159")
        (field (name "MANUFACTURER") "STMICROELECTRONICS")
        (field (name "PROVIDED_BY") "Subcon")
      )
      (libsource (lib "MCD_PARTS_database") (part "STMPS2151STR"))
    )
    (comp (ref "U3")
      (value "ECMF02-2AMX6")
      (footprint "MCD_PARTS:ESD_QFN-6L_1P7X1P5_P050")
      (description "Common mode filter with ESD protection for USB 2.0 interface")
      (fields (field (name "INTERNAL_PART_NUMBER") "MCD-00649") (field (name "BMS_PART_NUMBER") "9151138"))
      (libsource (lib "MCD_PARTS_database") (part "ECMF02-2AMX6"))
    )
    (comp (ref "U4")
      (value "ESDALC6V1W5")
      (footprint "MCD_PARTS:ESD_SOT323-5L")
      (description "Dual Transil array for ESD protection")
      (fields (field (name "INTERNAL_PART_NUMBER") "MCD-00136") (field (name "BMS_PART_NUMBER") "9151112"))
      (libsource (lib "MCD_PARTS_database") (part "ESDALC6V1W5"))
    )
    (comp (ref "U5")
      (value "ESDALC6V1-1U2")
      (footprint "MCD_PARTS:ESD_ST0201")
      (description "ESD protection 6V1")
      (fields (field (name "INTERNAL_PART_NUMBER") "MCD-00170") (field (name "BMS_PART_NUMBER") "9151132"))
      (libsource (lib "") (part "ESD-TRANSIL_1"))
    )
    (comp (ref "U6")
      (value "ESDA25P35-1U1M")
      (footprint "MCD_PARTS:ESD_QFN1610_2N_1K_2A")
      (description "High power Transient voltage suppressor:25V/35A EOS and ESD transients protection.")
      (fields
        (field (name "INTERNAL_PART_NUMBER") "MCD-01207")
        (field (name "MANUFACTURER") "STMICROELECTRONICS")
        (field (name "PROVIDED_BY") "SUBCO with ST control")
      )
      (libsource (lib "MCD_PARTS_database") (part "ESD-TRANSIL"))
    )
    (comp (ref "U7")
      (value "STM32F723IEK6")
      (footprint "MCD_PARTS:ICC_UFBGA201_176+25_10X10_P065")
      (description "MCU, Arm Cortex-M7 32-bit MCU, 512KB Flash, 276KB RAM, With Crypto")
      (fields (field (name "INTERNAL_PART_NUMBER") "MCD-02706") (field (name "BMS_PART_NUMBER") "9175300"))
      (libsource (lib "MCD_PARTS_database") (part "STLINK-V3EC"))
    )
    (comp (ref "U8")
      (value "TPS259535DSG")
      (footprint "MCD_PARTS:ICC_WSON8-EPAD_2X2_P050")
      (description "eFuse with Fast Overvoltage Protection 2.7V to 18V 4A 34mOhm 8-Pin WSON")
      (fields
        (field (name "INTERNAL_PART_NUMBER") "MCD-02532")
        (field (name "MANUFACTURER") "TEXAS INSTRUMENTS")
      )
      (libsource (lib "MCD_PARTS_database") (part "TPS259535DSG"))
    )
    (comp (ref "U9")
      (value "ST730M33R")
      (footprint "MCD_PARTS:ICC_SOT23-5L_H1P45")
      (description "LDO, 3.3V, 300mA, High input voltage: 2.5V to 28V, SOT23-5L")
      (fields
        (field (name "INTERNAL_PART_NUMBER") "MCD-02514")
        (field (name "MANUFACTURER") "STMICROELECTRONICS")
      )
      (libsource (lib "MCD_PARTS_database") (part "ST730M33R"))
    )
    (comp (ref "U10")
      (value "74AVC4TD245BQ")
      (footprint "MCD_PARTS:ICC_DHVQFN16-EPAD_SOT763-1_2P5X3P5_H0P85_P050")
      (description "4-bit dual supply translating transceiver with configurable voltage translation; 3-state")
      (fields
        (field (name "INTERNAL_PART_NUMBER") "MCD-01945")
        (field (name "MANUFACTURER_PART_NUMBER") "74AVC4TD245BQ,115")
      )
      (libsource (lib "MCD_PARTS_database") (part "74AVC4TD245BQ"))
    )
    (comp (ref "U23")
      (value "ESDALC6V1-1U2")
      (footprint "MCD_PARTS:ESD_ST0201")
      (description "ESD protection 6V1")
      (fields (field (name "INTERNAL_PART_NUMBER") "MCD-00170") (field (name "BMS_PART_NUMBER") "9151132"))
      (libsource (lib "") (part "ESD-TRANSIL_1"))
    )
    (comp (ref "U24")
      (value "ESDALC6V1W5")
      (footprint "MCD_PARTS:ESD_SOT323-5L")
      (description "Dual Transil array for ESD protection")
      (fields (field (name "INTERNAL_PART_NUMBER") "MCD-00136") (field (name "BMS_PART_NUMBER") "9151112"))
      (libsource (lib "MCD_PARTS_database") (part "ESDALC6V1W5"))
    )
    (comp (ref "X1")
      (value "24MHz")
      (footprint "MCD_PARTS:CRY_NX2016SA_4P")
      (description "Crystal, 24MHz, 6pF, +/-20ppm, 80R, 2x1.6mm")
      (fields (field (name "INTERNAL_PART_NUMBER") "MCD-01036") (field (name "BMS_PART_NUMBER") "9157045"))
      (libsource (lib "MCD_PARTS_database") (part "XTAL_4_PINS"))
    )
  )
  (nets
    (net (code "1") (name "/HiZ_DBG_IF_EN") (class "Default")
      (node (ref "JP1") (pin "2") (pinfunction "NO_2") (pintype "passive"))
      (node (ref "R94") (pin "2") (pinfunction "2_2") (pintype "passive"))
      (node (ref "U1") (pin "9") (pinfunction "~{OE}_9") (pintype "passive"))
    )
    (net (code "2") (name "/JTCK") (class "Default")
      (node (ref "CN5") (pin "4") (pinfunction "4_4") (pintype "passive"))
      (node (ref "R83") (pin "2") (pinfunction "2_2") (pintype "passive"))
      (node (ref "U10") (pin "11") (pinfunction "B4_11") (pintype "passive"))
      (node (ref "U24") (pin "4") (pinfunction "IO3_4") (pintype "passive"))
    )
    (net (code "3") (name "/JTDI") (class "Default")
      (node (ref "CN5") (pin "8") (pinfunction "8_8") (pintype "passive"))
      (node (ref "R92") (pin "2") (pinfunction "2_2") (pintype "passive"))
      (node (ref "U24") (pin "1") (pinfunction "IO1_1") (pintype "passive"))
    )
    (net (code "4") (name "/JTDO") (class "Default")
      (node (ref "CN5") (pin "6") (pinfunction "6_6") (pintype "passive"))
      (node (ref "R21") (pin "1") (pinfunction "1_1") (pintype "passive"))
      (node (ref "U10") (pin "13") (pinfunction "B2_13") (pintype "passive"))
      (node (ref "U24") (pin "3") (pinfunction "IO2_3") (pintype "passive"))
    )
    (net (code "5") (name "/JTMS") (class "Default")
      (node (ref "CN5") (pin "2") (pinfunction "2_2") (pintype "passive"))
      (node (ref "R84") (pin "2") (pinfunction "2_2") (pintype "passive"))
      (node (ref "U24") (pin "5") (pinfunction "IO4_5") (pintype "passive"))
    )
    (net (code "6") (name "/NRST") (class "Default")
      (node (ref "CN5") (pin "10") (pinfunction "10_10") (pintype "passive"))
      (node (ref "R91") (pin "2") (pinfunction "2_2") (pintype "passive"))
      (node (ref "U23") (pin "1") (pinfunction "IO1_1") (pintype "passive"))
    )
    (net (code "7") (name "/STLK_LED") (class "Default")
      (node (ref "R8") (pin "1") (pinfunction "1_1") (pintype "passive"))
      (node (ref "R9") (pin "2") (pinfunction "2_2") (pintype "passive"))
      (node (ref "U7") (pin "D15") (pinfunction "STLK_LED/PA10_D15") (pintype "passive"))
    )
    (net (code "8") (name "/STLK_MCO") (class "Default")
      (node (ref "C35") (pin "1") (pinfunction "1_1") (pintype "passive"))
      (node (ref "R77") (pin "2") (pinfunction "2_2") (pintype "passive"))
    )
    (net (code "9") (name "/STLK_OSC_IN") (class "Default")
      (node (ref "C20") (pin "2") (pinfunction "2_2") (pintype "passive"))
      (node (ref "U7") (pin "G1") (pinfunction "OSC_IN/PH0_G1") (pintype "passive"))
      (node (ref "X1") (pin "1") (pinfunction "1_1") (pintype "passive"))
    )
    (net (code "10") (name "/STLK_OSC_OUT") (class "Default")
      (node (ref "C24") (pin "2") (pinfunction "2_2") (pintype "passive"))
      (node (ref "U7") (pin "H1") (pinfunction "OSC_OUT/PH1_H1") (pintype "passive"))
      (node (ref "X1") (pin "3") (pinfunction "3_3") (pintype "passive"))
    )
    (net (code "11") (name "/STLK_SWCLK") (class "Default")
      (node (ref "CN2") (pin "2") (pinfunction "2_2") (pintype "passive"))
      (node (ref "U7") (pin "A14") (pinfunction "STLK_SWCLK/PA14_A14") (pintype "passive"))
    )
    (net (code "12") (name "/STLK_SWDIO") (class "Default")
      (node (ref "CN2") (pin "4") (pinfunction "4_4") (pintype "passive"))
      (node (ref "U7") (pin "A15") (pinfunction "STLK_SWDIO/PA13_A15") (pintype "passive"))
    )
    (net (code "13") (name "/STLK_UCPD_CC1_C") (class "Default")
      (node (ref "C5") (pin "1") (pinfunction "1_1") (pintype "passive"))
      (node (ref "R27") (pin "2") (pinfunction "2_2") (pintype "passive"))
      (node (ref "U7") (pin "M5") (pinfunction "ADCx_IN13/PC3_M5") (pintype "passive"))
    )
    (net (code "14") (name "/STLK_UCPD_CC2_C") (class "Default")
      (node (ref "C19") (pin "1") (pinfunction "1_1") (pintype "passive"))
      (node (ref "R64") (pin "2") (pinfunction "2_2") (pintype "passive"))
      (node (ref "U7") (pin "N5") (pinfunction "ADCx_IN14/PC4_N5") (pintype "passive"))
    )
    (net (code "15") (name "/STLK_USB_CN_N") (class "Default")
      (node (ref "CN1") (pin "A7") (pinfunction "D-1_A7") (pintype "passive"))
      (node (ref "CN1") (pin "B7") (pinfunction "D-2_B7") (pintype "passive"))
      (node (ref "U3") (pin "2") (pinfunction "D-_2") (pintype "passive"))
    )
    (net (code "16") (name "/STLK_USB_CN_P") (class "Default")
      (node (ref "CN1") (pin "A6") (pinfunction "D+1_A6") (pintype "passive"))
      (node (ref "CN1") (pin "B6") (pinfunction "D+2_B6") (pintype "passive"))
      (node (ref "U3") (pin "1") (pinfunction "D+_1") (pintype "passive"))
    )
    (net (code "17") (name "/STLK_USB_N") (class "Default")
      (node (ref "U3") (pin "5") (pinfunction "D-_5") (pintype "passive"))
      (node (ref "U7") (pin "R14") (pinfunction "USB_DEV_HS_N/PB14_R14") (pintype "passive"))
    )
    (net (code "18") (name "/STLK_USB_P") (class "Default")
      (node (ref "U3") (pin "6") (pinfunction "D+_6") (pintype "passive"))
      (node (ref "U7") (pin "R15") (pinfunction "USB_DEV_HS_P/PB15_R15") (pintype "passive"))
    )
    (net (code "19") (name "/STLK_VCP_RX") (class "Default")
      (node (ref "R16") (pin "1") (pinfunction "1_1") (pintype "passive"))
      (node (ref "U10") (pin "5") (pinfunction "A3_5") (pintype "passive"))
      (node (ref "U7") (pin "C10") (pinfunction "STLK_VCP_RX/PG9_C10") (pintype "passive"))
    )
    (net (code "20") (name "/STLK_VCP_TX") (class "Default")
      (node (ref "R95") (pin "2") (pinfunction "2_2") (pintype "passive"))
      (node (ref "U1") (pin "3") (pinfunction "A1_3") (pintype "passive"))
      (node (ref "U7") (pin "A7") (pinfunction "STLK_VCP_TX/PG14_A7") (pintype "passive"))
    )
    (net (code "21") (name "/SW_DIR") (class "Default")
      (node (ref "R22") (pin "2") (pinfunction "2_2") (pintype "passive"))
      (node (ref "U1") (pin "10") (pinfunction "DIR3_10") (pintype "passive"))
      (node (ref "U7") (pin "R3") (pinfunction "T_SW_DIR/PA7_R3") (pintype "passive"))
    )
    (net (code "22") (name "/TRACECLK") (class "Default")
      (node (ref "CN5") (pin "12") (pinfunction "12_12") (pintype "passive"))
      (node (ref "R89") (pin "1") (pinfunction "1_1") (pintype "passive"))
      (node (ref "U5") (pin "1") (pinfunction "IO1_1") (pintype "passive"))
    )
    (net (code "23") (name "/TRACED0") (class "Default")
      (node (ref "CN5") (pin "14") (pinfunction "14_14") (pintype "passive"))
      (node (ref "R97") (pin "1") (pinfunction "1_1") (pintype "passive"))
      (node (ref "U4") (pin "4") (pinfunction "IO3_4") (pintype "passive"))
    )
    (net (code "24") (name "/TRACED1") (class "Default")
      (node (ref "CN5") (pin "16") (pinfunction "16_16") (pintype "passive"))
      (node (ref "R98") (pin "1") (pinfunction "1_1") (pintype "passive"))
      (node (ref "U4") (pin "3") (pinfunction "IO2_3") (pintype "passive"))
    )
    (net (code "25") (name "/TRACED2") (class "Default")
      (node (ref "CN5") (pin "18") (pinfunction "18_18") (pintype "passive"))
      (node (ref "R99") (pin "1") (pinfunction "1_1") (pintype "passive"))
      (node (ref "U4") (pin "1") (pinfunction "IO1_1") (pintype "passive"))
    )
    (net (code "26") (name "/TRACED3") (class "Default")
      (node (ref "CN5") (pin "20") (pinfunction "20_20") (pintype "passive"))
      (node (ref "R100") (pin "1") (pinfunction "1_1") (pintype "passive"))
      (node (ref "U4") (pin "5") (pinfunction "IO4_5") (pintype "passive"))
    )
    (net (code "27") (name "/TRACE_CK") (class "Default")
      (node (ref "R89") (pin "2") (pinfunction "2_2") (pintype "passive"))
    )
    (net (code "28") (name "/TRACE_D0") (class "Default")
      (node (ref "R97") (pin "2") (pinfunction "2_2") (pintype "passive"))
    )
    (net (code "29") (name "/TRACE_D1") (class "Default")
      (node (ref "R98") (pin "2") (pinfunction "2_2") (pintype "passive"))
    )
    (net (code "30") (name "/TRACE_D2") (class "Default")
      (node (ref "R99") (pin "2") (pinfunction "2_2") (pintype "passive"))
    )
    (net (code "31") (name "/TRACE_D3") (class "Default")
      (node (ref "R100") (pin "2") (pinfunction "2_2") (pintype "passive"))
    )
    (net (code "32") (name "/T_JRCLK") (class "Default")
      (node (ref "R19") (pin "1") (pinfunction "1_1") (pintype "passive"))
      (node (ref "U10") (pin "6") (pinfunction "A4_6") (pintype "passive"))
      (node (ref "U7") (pin "A10") (pinfunction "T_JRCLK/PB3_A10") (pintype "passive"))
    )
    (net (code "33") (name "/T_JTDI") (class "Default")
      (node (ref "R81") (pin "1") (pinfunction "1_1") (pintype "passive"))
      (node (ref "U1") (pin "6") (pinfunction "A4_6") (pintype "passive"))
      (node (ref "U7") (pin "L3") (pinfunction "T_JTDI/PF8_L3") (pintype "passive"))
    )
    (net (code "34") (name "/T_MCO") (class "Default")
      (node (ref "R5") (pin "2") (pinfunction "2_2") (pintype "passive"))
      (node (ref "R78") (pin "2") (pinfunction "2_2") (pintype "passive"))
      (node (ref "TP13") (pin "1") (pinfunction "1_1") (pintype "passive"))
      (node (ref "U10") (pin "3") (pinfunction "A1_3") (pintype "passive"))
    )
    (net (code "35") (name "/T_PWR_EN") (class "Default")
      (node (ref "R7") (pin "2") (pinfunction "2_2") (pintype "passive"))
      (node (ref "R93") (pin "2") (pinfunction "2_2") (pintype "passive"))
      (node (ref "U2") (pin "4") (pinfunction "EN_4") (pintype "passive"))
      (node (ref "U7") (pin "R5") (pinfunction "T_PWR_EN/PB0_R5") (pintype "passive"))
      (node (ref "U8") (pin "2") (pinfunction "EN/UVLO_2") (pintype "passive"))
    )
    (net (code "36") (name "/T_PWR_EXT") (class "Default")
      (node (ref "R14") (pin "1") (pinfunction "1_1") (pintype "passive"))
      (node (ref "R15") (pin "1") (pinfunction "1_1") (pintype "passive"))
      (node (ref "U7") (pin "R4") (pinfunction "T_PWR_EXT/PB1_R4") (pintype "passive"))
    )
    (net (code "37") (name "/T_PWR_INT") (class "Default")
      (node (ref "R1") (pin "2") (pinfunction "2_2") (pintype "passive"))
      (node (ref "R2") (pin "2") (pinfunction "2_2") (pintype "passive"))
      (node (ref "R85") (pin "2") (pinfunction "2_2") (pintype "passive"))
      (node (ref "U2") (pin "3") (pinfunction "~{FAULT}_3") (pintype "passive"))
      (node (ref "U7") (pin "B13") (pinfunction "T_PWR_INT/PC11_B13") (pintype "passive"))
    )
    (net (code "38") (name "/T_PWR_LED") (class "Default")
      (node (ref "R3") (pin "2") (pinfunction "2_2") (pintype "passive"))
      (node (ref "R4") (pin "2") (pinfunction "2_2") (pintype "passive"))
      (node (ref "U7") (pin "H15") (pinfunction "T_PWR_LED/PC6_H15") (pintype "passive"))
    )
    (net (code "39") (name "/T_PWR_SEL1") (class "Default")
      (node (ref "R86") (pin "2") (pinfunction "2_2") (pintype "passive"))
      (node (ref "U7") (pin "D10") (pinfunction "T_PWR_SEL1/PD4_D10") (pintype "passive"))
    )
    (net (code "40") (name "/T_PWR_SEL2") (class "Default")
      (node (ref "R87") (pin "2") (pinfunction "2_2") (pintype "passive"))
      (node (ref "U7") (pin "C11") (pinfunction "T_PWR_SEL2/PD5_C11") (pintype "passive"))
    )
    (net (code "41") (name "/T_SWCLK") (class "Default")
      (node (ref "R79") (pin "2") (pinfunction "2_2") (pintype "passive"))
      (node (ref "U1") (pin "4") (pinfunction "A2_4") (pintype "passive"))
      (node (ref "U7") (pin "M11") (pinfunction "T_SWCLK/PH6_M11") (pintype "passive"))
      (node (ref "U7") (pin "M6") (pinfunction "T_JCLK_OUT/PB2_M6") (pintype "passive"))
    )
    (net (code "42") (name "/T_SWDIO") (class "Default")
      (node (ref "R80") (pin "1") (pinfunction "1_1") (pintype "passive"))
      (node (ref "U1") (pin "5") (pinfunction "A3_5") (pintype "passive"))
      (node (ref "U7") (pin "L2") (pinfunction "T_JTMS/T_SWDIO_OUT/PF9_L2") (pintype "passive"))
      (node (ref "U7") (pin "N12") (pinfunction "T_SWDIO_IN/PH7_N12") (pintype "passive"))
    )
    (net (code "43") (name "/T_SWO") (class "Default")
      (node (ref "R13") (pin "1") (pinfunction "1_1") (pintype "passive"))
      (node (ref "U10") (pin "4") (pinfunction "A2_4") (pintype "passive"))
      (node (ref "U7") (pin "A6") (pinfunction "T_JTDO/PB5_A6") (pintype "passive"))
      (node (ref "U7") (pin "D12") (pinfunction "T_SWO/PD2_D12") (pintype "passive"))
    )
    (net (code "44") (name "/T_VCC_AIN") (class "Default")
      (node (ref "R17") (pin "1") (pinfunction "1_1") (pintype "passive"))
      (node (ref "R18") (pin "1") (pinfunction "1_1") (pintype "passive"))
      (node (ref "U7") (pin "N3") (pinfunction "T_VCC_AIN/PA0_N3") (pintype "passive"))
    )
    (net (code "45") (name "/T_VCP_RX") (class "Default")
      (node (ref "R82") (pin "2") (pinfunction "2_2") (pintype "passive"))
    )
    (net (code "46") (name "/T_VCP_TX") (class "Default")
      (node (ref "R20") (pin "1") (pinfunction "1_1") (pintype "passive"))
      (node (ref "U10") (pin "12") (pinfunction "B3_12") (pintype "passive"))
    )
    (net (code "47") (name "3V3_STLK") (class "Default")
      (node (ref "C10") (pin "1") (pinfunction "1_1") (pintype "passive"))
      (node (ref "C11") (pin "1") (pinfunction "1_1") (pintype "passive"))
      (node (ref "C13") (pin "1") (pinfunction "1_1") (pintype "passive"))
      (node (ref "C15") (pin "1") (pinfunction "1_1") (pintype "passive"))
      (node (ref "C16") (pin "1") (pinfunction "1_1") (pintype "passive"))
      (node (ref "C17") (pin "1") (pinfunction "1_1") (pintype "passive"))
      (node (ref "C21") (pin "1") (pinfunction "1_1") (pintype "passive"))
      (node (ref "C22") (pin "1") (pinfunction "1_1") (pintype "passive"))
      (node (ref "C23") (pin "2") (pinfunction "2_2") (pintype "passive"))
      (node (ref "C25") (pin "1") (pinfunction "1_1") (pintype "passive"))
      (node (ref "C26") (pin "2") (pinfunction "2_2") (pintype "passive"))
      (node (ref "C29") (pin "1") (pinfunction "1_1") (pintype "passive"))
      (node (ref "C30") (pin "1") (pinfunction "1_1") (pintype "passive"))
      (node (ref "C31") (pin "1") (pinfunction "1_1") (pintype "passive"))
      (node (ref "C32") (pin "1") (pinfunction "1_1") (pintype "passive"))
      (node (ref "C33") (pin "1") (pinfunction "1_1") (pintype "passive"))
      (node (ref "C34") (pin "1") (pinfunction "1_1") (pintype "passive"))
      (node (ref "C4") (pin "2") (pinfunction "2_2") (pintype "passive"))
      (node (ref "C8") (pin "1") (pinfunction "1_1") (pintype "passive"))
      (node (ref "C9") (pin "1") (pinfunction "1_1") (pintype "passive"))
      (node (ref "CN2") (pin "1") (pinfunction "1_1") (pintype "passive"))
      (node (ref "JP1") (pin "1") (pinfunction "COMMON_1") (pintype "passive"))
      (node (ref "LD4") (pin "4") (pinfunction "Green_anode_4") (pintype "passive"))
      (node (ref "LD6") (pin "4") (pinfunction "Green_anode_4") (pintype "passive"))
      (node (ref "R1") (pin "1") (pinfunction "1_1") (pintype "passive"))
      (node (ref "R10") (pin "2") (pinfunction "2_2") (pintype "passive"))
      (node (ref "R13") (pin "2") (pinfunction "2_2") (pintype "passive"))
      (node (ref "R16") (pin "2") (pinfunction "2_2") (pintype "passive"))
      (node (ref "R19") (pin "2") (pinfunction "2_2") (pintype "passive"))
      (node (ref "R79") (pin "1") (pinfunction "1_1") (pintype "passive"))
      (node (ref "R80") (pin "2") (pinfunction "2_2") (pintype "passive"))
      (node (ref "R81") (pin "2") (pinfunction "2_2") (pintype "passive"))
      (node (ref "R95") (pin "1") (pinfunction "1_1") (pintype "passive"))
      (node (ref "U1") (pin "1") (pinfunction "VCCA_1") (pintype "passive"))
      (node (ref "U1") (pin "15") (pinfunction "DIR2_15") (pintype "passive"))
      (node (ref "U1") (pin "2") (pinfunction "DIR1_2") (pintype "passive"))
      (node (ref "U1") (pin "7") (pinfunction "DIR4_7") (pintype "passive"))
      (node (ref "U10") (pin "1") (pinfunction "VCCA_1") (pintype "passive"))
      (node (ref "U10") (pin "2") (pinfunction "DIR1_2") (pintype "passive"))
      (node (ref "U7") (pin "C1") (pinfunction "VBAT_C1") (pintype "passive"))
      (node (ref "U7") (pin "C5") (pinfunction "VDD_C5") (pintype "passive"))
      (node (ref "U7") (pin "C6") (pinfunction "PDR_ON_C6") (pintype "passive"))
      (node (ref "U7") (pin "C7") (pinfunction "VDD_C7") (pintype "passive"))
      (node (ref "U7") (pin "C8") (pinfunction "VDD_C8") (pintype "passive"))
      (node (ref "U7") (pin "C9") (pinfunction "VDD_C9") (pintype "passive"))
      (node (ref "U7") (pin "F3") (pinfunction "VDD_F3") (pintype "passive"))
      (node (ref "U7") (pin "G13") (pinfunction "VDD_G13") (pintype "passive"))
      (node (ref "U7") (pin "G3") (pinfunction "VDD_G3") (pintype "passive"))
      (node (ref "U7") (pin "H13") (pinfunction "VDD_H13") (pintype "passive"))
      (node (ref "U7") (pin "J12") (pinfunction "VDD_J12") (pintype "passive"))
      (node (ref "U7") (pin "J13") (pinfunction "VDD_J13") (pintype "passive"))
      (node (ref "U7") (pin "K4") (pinfunction "VDD_K4") (pintype "passive"))
      (node (ref "U7") (pin "N10") (pinfunction "VDD_N10") (pintype "passive"))
      (node (ref "U7") (pin "N8") (pinfunction "VDD_N8") (pintype "passive"))
      (node (ref "U7") (pin "N9") (pinfunction "VDD_N9") (pintype "passive"))
      (node (ref "U7") (pin "P1") (pinfunction "VREF+_P1") (pintype "passive"))
      (node (ref "U7") (pin "R1") (pinfunction "VDDA_R1") (pintype "passive"))
      (node (ref "U9") (pin "1") (pinfunction "VOUT_1") (pintype "passive"))
    )
    (net (code "48") (name "5V") (class "Default")
      (node (ref "R14") (pin "2") (pinfunction "2_2") (pintype "passive"))
    )
    (net (code "49") (name "5V_STLK") (class "Default")
      (node (ref "C1") (pin "2") (pinfunction "2_2") (pintype "passive"))
      (node (ref "C36") (pin "2") (pinfunction "2_2") (pintype "passive"))
      (node (ref "R2") (pin "1") (pinfunction "1_1") (pintype "passive"))
      (node (ref "U2") (pin "1") (pinfunction "OUT_1") (pintype "passive"))
      (node (ref "U8") (pin "5") (pinfunction "OUT_5") (pintype "passive"))
      (node (ref "U8") (pin "6") (pinfunction "QOD_6") (pintype "passive"))
    )
    (net (code "50") (name "GND") (class "Default")
      (node (ref "C1") (pin "1") (pinfunction "1_1") (pintype "passive"))
      (node (ref "C10") (pin "2") (pinfunction "2_2") (pintype "passive"))
      (node (ref "C11") (pin "2") (pinfunction "2_2") (pintype "passive"))
      (node (ref "C12") (pin "1") (pinfunction "1_1") (pintype "passive"))
      (node (ref "C13") (pin "2") (pinfunction "2_2") (pintype "passive"))
      (node (ref "C14") (pin "1") (pinfunction "1_1") (pintype "passive"))
      (node (ref "C15") (pin "2") (pinfunction "2_2") (pintype "passive"))
      (node (ref "C16") (pin "2") (pinfunction "2_2") (pintype "passive"))
      (node (ref "C17") (pin "2") (pinfunction "2_2") (pintype "passive"))
      (node (ref "C18") (pin "1") (pinfunction "1_1") (pintype "passive"))
      (node (ref "C19") (pin "2") (pinfunction "2_2") (pintype "passive"))
      (node (ref "C2") (pin "2") (pinfunction "2_2") (pintype "passive"))
      (node (ref "C20") (pin "1") (pinfunction "1_1") (pintype "passive"))
      (node (ref "C21") (pin "2") (pinfunction "2_2") (pintype "passive"))
      (node (ref "C22") (pin "2") (pinfunction "2_2") (pintype "passive"))
      (node (ref "C23") (pin "1") (pinfunction "1_1") (pintype "passive"))
      (node (ref "C24") (pin "1") (pinfunction "1_1") (pintype "passive"))
      (node (ref "C25") (pin "2") (pinfunction "2_2") (pintype "passive"))
      (node (ref "C26") (pin "1") (pinfunction "1_1") (pintype "passive"))
      (node (ref "C27") (pin "2") (pinfunction "2_2") (pintype "passive"))
      (node (ref "C28") (pin "1") (pinfunction "1_1") (pintype "passive"))
      (node (ref "C29") (pin "2") (pinfunction "2_2") (pintype "passive"))
      (node (ref "C3") (pin "1") (pinfunction "1_1") (pintype "passive"))
      (node (ref "C30") (pin "2") (pinfunction "2_2") (pintype "passive"))
      (node (ref "C31") (pin "2") (pinfunction "2_2") (pintype "passive"))
      (node (ref "C32") (pin "2") (pinfunction "2_2") (pintype "passive"))
      (node (ref "C33") (pin "2") (pinfunction "2_2") (pintype "passive"))
      (node (ref "C34") (pin "2") (pinfunction "2_2") (pintype "passive"))
      (node (ref "C35") (pin "2") (pinfunction "2_2") (pintype "passive"))
      (node (ref "C36") (pin "1") (pinfunction "1_1") (pintype "passive"))
      (node (ref "C37") (pin "1") (pinfunction "1_1") (pintype "passive"))
      (node (ref "C4") (pin "1") (pinfunction "1_1") (pintype "passive"))
      (node (ref "C5") (pin "2") (pinfunction "2_2") (pintype "passive"))
      (node (ref "C6") (pin "2") (pinfunction "2_2") (pintype "passive"))
      (node (ref "C7") (pin "1") (pinfunction "1_1") (pintype "passive"))
      (node (ref "C8") (pin "2") (pinfunction "2_2") (pintype "passive"))
      (node (ref "C9") (pin "2") (pinfunction "2_2") (pintype "passive"))
      (node (ref "C92") (pin "1") (pinfunction "1_1") (pintype "passive"))
      (node (ref "CN1") (pin "A1") (pinfunction "GND1_A1") (pintype "passive"))
      (node (ref "CN1") (pin "A12") (pinfunction "GND2_A12") (pintype "passive"))
      (node (ref "CN1") (pin "B1") (pinfunction "GND3_B1") (pintype "passive"))
      (node (ref "CN1") (pin "B12") (pinfunction "GND4_B12") (pintype "passive"))
      (node (ref "CN1") (pin "SH1") (pinfunction "Shield1_SH1") (pintype "passive"))
      (node (ref "CN1") (pin "SH2") (pinfunction "Shield2_SH2") (pintype "passive"))
      (node (ref "CN1") (pin "SH3") (pinfunction "Shield3_SH3") (pintype "passive"))
      (node (ref "CN1") (pin "SH4") (pinfunction "Shield4_SH4") (pintype "passive"))
      (node (ref "CN2") (pin "3") (pinfunction "3_3") (pintype "passive"))
      (node (ref "CN3") (pin "1") (pinfunction "COMMON_1") (pintype "passive"))
      (node (ref "CN3") (pin "2") (pinfunction "NO_2") (pintype "passive"))
      (node (ref "CN4") (pin "1") (pinfunction "COMMON_1") (pintype "passive"))
      (node (ref "CN4") (pin "2") (pinfunction "NO_2") (pintype "passive"))
      (node (ref "CN5") (pin "15") (pinfunction "15_15") (pintype "passive"))
      (node (ref "CN5") (pin "17") (pinfunction "17_17") (pintype "passive"))
      (node (ref "CN5") (pin "19") (pinfunction "19_19") (pintype "passive"))
      (node (ref "CN5") (pin "3") (pinfunction "3_3") (pintype "passive"))
      (node (ref "CN5") (pin "5") (pinfunction "5_5") (pintype "passive"))
      (node (ref "CN5") (pin "9") (pinfunction "9_9") (pintype "passive"))
      (node (ref "JP3") (pin "2") (pinfunction "NO_2") (pintype "passive"))
      (node (ref "LD4") (pin "3") (pinfunction "RED_cathode_3") (pintype "passive"))
      (node (ref "LD6") (pin "3") (pinfunction "RED_cathode_3") (pintype "passive"))
      (node (ref "R11") (pin "2") (pinfunction "2_2") (pintype "passive"))
      (node (ref "R15") (pin "2") (pinfunction "2_2") (pintype "passive"))
      (node (ref "R17") (pin "2") (pinfunction "2_2") (pintype "passive"))
      (node (ref "R22") (pin "1") (pinfunction "1_1") (pintype "passive"))
      (node (ref "R6") (pin "2") (pinfunction "2_2") (pintype "passive"))
      (node (ref "R7") (pin "1") (pinfunction "1_1") (pintype "passive"))
      (node (ref "R76") (pin "2") (pinfunction "2_2") (pintype "passive"))
      (node (ref "R78") (pin "1") (pinfunction "1_1") (pintype "passive"))
      (node (ref "R85") (pin "1") (pinfunction "1_1") (pintype "passive"))
      (node (ref "R88") (pin "2") (pinfunction "2_2") (pintype "passive"))
      (node (ref "R93") (pin "1") (pinfunction "1_1") (pintype "passive"))
      (node (ref "R94") (pin "1") (pinfunction "1_1") (pintype "passive"))
      (node (ref "SB84") (pin "1") (pinfunction "1_1") (pintype "passive"))
      (node (ref "U1") (pin "17") (pinfunction "EP_17") (pintype "passive"))
      (node (ref "U1") (pin "8") (pinfunction "GND_8") (pintype "passive"))
      (node (ref "U10") (pin "10") (pinfunction "DIR3_10") (pintype "passive"))
      (node (ref "U10") (pin "15") (pinfunction "DIR2_15") (pintype "passive"))
      (node (ref "U10") (pin "17") (pinfunction "EP_17") (pintype "passive"))
      (node (ref "U10") (pin "7") (pinfunction "DIR4_7") (pintype "passive"))
      (node (ref "U10") (pin "8") (pinfunction "GND_8") (pintype "passive"))
      (node (ref "U10") (pin "9") (pinfunction "~{OE}_9") (pintype "passive"))
      (node (ref "U2") (pin "2") (pinfunction "GND_2") (pintype "passive"))
      (node (ref "U23") (pin "2") (pinfunction "GND_2") (pintype "passive"))
      (node (ref "U24") (pin "2") (pinfunction "GND_2") (pintype "passive"))
      (node (ref "U3") (pin "3") (pinfunction "GND_3") (pintype "passive"))
      (node (ref "U4") (pin "2") (pinfunction "GND_2") (pintype "passive"))
      (node (ref "U5") (pin "2") (pinfunction "GND_2") (pintype "passive"))
      (node (ref "U6") (pin "2") (pinfunction "GND_2") (pintype "passive"))
      (node (ref "U7") (pin "D5") (pinfunction "VSS_D5") (pintype "passive"))
      (node (ref "U7") (pin "D6") (pinfunction "BOOT0_D6") (pintype "passive"))
      (node (ref "U7") (pin "D7") (pinfunction "VSS_D7") (pintype "passive"))
      (node (ref "U7") (pin "D8") (pinfunction "VSS_D8") (pintype "passive"))
      (node (ref "U7") (pin "D9") (pinfunction "VSS_D9") (pintype "passive"))
      (node (ref "U7") (pin "F10") (pinfunction "VSS_F10") (pintype "passive"))
      (node (ref "U7") (pin "F12") (pinfunction "VSS_F12") (pintype "passive"))
      (node (ref "U7") (pin "F2") (pinfunction "VSS_F2") (pintype "passive"))
      (node (ref "U7") (pin "F6") (pinfunction "VSS_F6") (pintype "passive"))
      (node (ref "U7") (pin "F7") (pinfunction "VSS_F7") (pintype "passive"))
      (node (ref "U7") (pin "F8") (pinfunction "VSS_F8") (pintype "passive"))
      (node (ref "U7") (pin "F9") (pinfunction "VSS_F9") (pintype "passive"))
      (node (ref "U7") (pin "G10") (pinfunction "VSS_G10") (pintype "passive"))
      (node (ref "U7") (pin "G12") (pinfunction "VSS_G12") (pintype "passive"))
      (node (ref "U7") (pin "G2") (pinfunction "VSS_G2") (pintype "passive"))
      (node (ref "U7") (pin "G6") (pinfunction "VSS_G6") (pintype "passive"))
      (node (ref "U7") (pin "G7") (pinfunction "VSS_G7") (pintype "passive"))
      (node (ref "U7") (pin "G8") (pinfunction "VSS_G8") (pintype "passive"))
      (node (ref "U7") (pin "G9") (pinfunction "VSS_G9") (pintype "passive"))
      (node (ref "U7") (pin "H10") (pinfunction "VSS_H10") (pintype "passive"))
      (node (ref "U7") (pin "H12") (pinfunction "VSS_H12") (pintype "passive"))
      (node (ref "U7") (pin "H6") (pinfunction "VSS_H6") (pintype "passive"))
      (node (ref "U7") (pin "H7") (pinfunction "VSS_H7") (pintype "passive"))
      (node (ref "U7") (pin "H8") (pinfunction "VSS_H8") (pintype "passive"))
      (node (ref "U7") (pin "H9") (pinfunction "VSS_H9") (pintype "passive"))
      (node (ref "U7") (pin "J10") (pinfunction "VSS_J10") (pintype "passive"))
      (node (ref "U7") (pin "J6") (pinfunction "VSS_J6") (pintype "passive"))
      (node (ref "U7") (pin "J7") (pinfunction "VSS_J7") (pintype "passive"))
      (node (ref "U7") (pin "J8") (pinfunction "VSS_J8") (pintype "passive"))
      (node (ref "U7") (pin "J9") (pinfunction "VSS_J9") (pintype "passive"))
      (node (ref "U7") (pin "K10") (pinfunction "VSS_K10") (pintype "passive"))
      (node (ref "U7") (pin "K6") (pinfunction "VSS_K6") (pintype "passive"))
      (node (ref "U7") (pin "K7") (pinfunction "VSS_K7") (pintype "passive"))
      (node (ref "U7") (pin "K8") (pinfunction "VSS_K8") (pintype "passive"))
      (node (ref "U7") (pin "K9") (pinfunction "VSS_K9") (pintype "passive"))
      (node (ref "U7") (pin "L4") (pinfunction "BYPASS-REG_L4") (pintype "passive"))
      (node (ref "U7") (pin "M1") (pinfunction "VSSA_M1") (pintype "passive"))
      (node (ref "U7") (pin "M8") (pinfunction "VSS_M8") (pintype "passive"))
      (node (ref "U7") (pin "M9") (pinfunction "VSS_M9") (pintype "passive"))
      (node (ref "U7") (pin "N1") (pinfunction "VREF-_N1") (pintype "passive"))
      (node (ref "U8") (pin "8") (pinfunction "GND_8") (pintype "passive"))
      (node (ref "U8") (pin "9") (pinfunction "EP_9") (pintype "passive"))
      (node (ref "U9") (pin "2") (pinfunction "GND_2") (pintype "passive"))
      (node (ref "X1") (pin "2") (pinfunction "2_2") (pintype "passive"))
      (node (ref "X1") (pin "4") (pinfunction "4_4") (pintype "passive"))
    )
    (net (code "51") (name "Net-(CN1-CC1)") (class "Default")
      (node (ref "CN1") (pin "A5") (pinfunction "CC1_A5") (pintype "passive"))
      (node (ref "R11") (pin "1") (pinfunction "1_1") (pintype "passive"))
      (node (ref "R27") (pin "1") (pinfunction "1_1") (pintype "passive"))
    )
    (net (code "52") (name "Net-(CN1-CC2)") (class "Default")
      (node (ref "CN1") (pin "B5") (pinfunction "CC2_B5") (pintype "passive"))
      (node (ref "R64") (pin "1") (pinfunction "1_1") (pintype "passive"))
      (node (ref "R76") (pin "1") (pinfunction "1_1") (pintype "passive"))
    )
    (net (code "53") (name "Net-(CN5-Pad11)") (class "Default")
      (node (ref "CN5") (pin "11") (pinfunction "11_11") (pintype "passive"))
      (node (ref "CN5") (pin "13") (pinfunction "13_13") (pintype "passive"))
      (node (ref "SB84") (pin "2") (pinfunction "2_2") (pintype "passive"))
    )
    (net (code "54") (name "Net-(JP3-COMMON)") (class "Default")
      (node (ref "C28") (pin "2") (pinfunction "2_2") (pintype "passive"))
      (node (ref "JP3") (pin "1") (pinfunction "COMMON_1") (pintype "passive"))
      (node (ref "U7") (pin "J1") (pinfunction "NRST_J1") (pintype "passive"))
    )
    (net (code "55") (name "Net-(LD4-Green_cathode)") (class "Default")
      (node (ref "LD4") (pin "2") (pinfunction "Green_cathode_2") (pintype "passive"))
      (node (ref "R8") (pin "2") (pinfunction "2_2") (pintype "passive"))
    )
    (net (code "56") (name "Net-(LD4-Red_anode)") (class "Default")
      (node (ref "LD4") (pin "1") (pinfunction "Red_anode_1") (pintype "passive"))
      (node (ref "R9") (pin "1") (pinfunction "1_1") (pintype "passive"))
    )
    (net (code "57") (name "Net-(LD6-Green_cathode)") (class "Default")
      (node (ref "LD6") (pin "2") (pinfunction "Green_cathode_2") (pintype "passive"))
      (node (ref "R3") (pin "1") (pinfunction "1_1") (pintype "passive"))
    )
    (net (code "58") (name "Net-(LD6-Red_anode)") (class "Default")
      (node (ref "LD6") (pin "1") (pinfunction "Red_anode_1") (pintype "passive"))
      (node (ref "R4") (pin "1") (pinfunction "1_1") (pintype "passive"))
    )
    (net (code "59") (name "Net-(U1-B1)") (class "Default")
      (node (ref "R82") (pin "1") (pinfunction "1_1") (pintype "passive"))
      (node (ref "U1") (pin "14") (pinfunction "B1_14") (pintype "passive"))
    )
    (net (code "60") (name "Net-(U1-B2)") (class "Default")
      (node (ref "R83") (pin "1") (pinfunction "1_1") (pintype "passive"))
      (node (ref "U1") (pin "13") (pinfunction "B2_13") (pintype "passive"))
    )
    (net (code "61") (name "Net-(U1-B3)") (class "Default")
      (node (ref "R84") (pin "1") (pinfunction "1_1") (pintype "passive"))
      (node (ref "R90") (pin "1") (pinfunction "1_1") (pintype "passive"))
      (node (ref "U1") (pin "12") (pinfunction "B3_12") (pintype "passive"))
    )
    (net (code "62") (name "Net-(U1-B4)") (class "Default")
      (node (ref "R92") (pin "1") (pinfunction "1_1") (pintype "passive"))
      (node (ref "U1") (pin "11") (pinfunction "B4_11") (pintype "passive"))
    )
    (net (code "63") (name "Net-(U7A-HW_TYP_0{slash}PI4)") (class "Default")
      (node (ref "R10") (pin "1") (pinfunction "1_1") (pintype "passive"))
      (node (ref "U7") (pin "D4") (pinfunction "HW_TYP_0/PI4_D4") (pintype "passive"))
    )
    (net (code "64") (name "Net-(U7A-REXT_OTGPHY)") (class "Default")
      (node (ref "R6") (pin "1") (pinfunction "1_1") (pintype "passive"))
      (node (ref "U7") (pin "J15") (pinfunction "REXT_OTGPHY_J15") (pintype "passive"))
    )
    (net (code "65") (name "Net-(U7A-T_MCO{slash}PA8)") (class "Default")
      (node (ref "R5") (pin "1") (pinfunction "1_1") (pintype "passive"))
      (node (ref "U7") (pin "F15") (pinfunction "T_MCO/PA8_F15") (pintype "passive"))
    )
    (net (code "66") (name "Net-(U7A-T_NRST{slash}PA6)") (class "Default")
      (node (ref "R91") (pin "1") (pinfunction "1_1") (pintype "passive"))
      (node (ref "U7") (pin "P3") (pinfunction "T_NRST/PA6_P3") (pintype "passive"))
    )
    (net (code "67") (name "Net-(U7A-V12_OTGPHY)") (class "Default")
      (node (ref "C7") (pin "2") (pinfunction "2_2") (pintype "passive"))
      (node (ref "U7") (pin "J14") (pinfunction "V12_OTGPHY_J14") (pintype "passive"))
    )
    (net (code "68") (name "Net-(U7B-VCAP1)") (class "Default")
      (node (ref "C14") (pin "2") (pinfunction "2_2") (pintype "passive"))
      (node (ref "U7") (pin "M10") (pinfunction "VCAP1_M10") (pintype "passive"))
    )
    (net (code "69") (name "Net-(U7B-VCAP2)") (class "Default")
      (node (ref "C12") (pin "2") (pinfunction "2_2") (pintype "passive"))
      (node (ref "U7") (pin "F13") (pinfunction "VCAP2_F13") (pintype "passive"))
    )
    (net (code "70") (name "Net-(U8-ILM)") (class "Default")
      (node (ref "R86") (pin "1") (pinfunction "1_1") (pintype "passive"))
      (node (ref "R87") (pin "1") (pinfunction "1_1") (pintype "passive"))
      (node (ref "R88") (pin "1") (pinfunction "1_1") (pintype "passive"))
      (node (ref "U8") (pin "7") (pinfunction "ILM_7") (pintype "passive"))
    )
    (net (code "71") (name "Net-(U8-dVdt)") (class "Default")
      (node (ref "C92") (pin "2") (pinfunction "2_2") (pintype "passive"))
      (node (ref "U8") (pin "1") (pinfunction "dVdt_1") (pintype "passive"))
    )
    (net (code "72") (name "Net-(U10-B1)") (class "Default")
      (node (ref "R77") (pin "1") (pinfunction "1_1") (pintype "passive"))
      (node (ref "U10") (pin "14") (pinfunction "B1_14") (pintype "passive"))
    )
    (net (code "73") (name "VBUS_STLK") (class "Default")
      (node (ref "C18") (pin "2") (pinfunction "2_2") (pintype "passive"))
      (node (ref "C3") (pin "2") (pinfunction "2_2") (pintype "passive"))
      (node (ref "C37") (pin "2") (pinfunction "2_2") (pintype "passive"))
      (node (ref "C6") (pin "1") (pinfunction "1_1") (pintype "passive"))
      (node (ref "CN1") (pin "A4") (pinfunction "VBUS1_A4") (pintype "passive"))
      (node (ref "CN1") (pin "A9") (pinfunction "VBUS2_A9") (pintype "passive"))
      (node (ref "CN1") (pin "B4") (pinfunction "VBUS3_B4") (pintype "passive"))
      (node (ref "CN1") (pin "B9") (pinfunction "VBUS4_B9") (pintype "passive"))
      (node (ref "U2") (pin "5") (pinfunction "IN_5") (pintype "passive"))
      (node (ref "U6") (pin "1") (pinfunction "IO1_1") (pintype "passive"))
      (node (ref "U8") (pin "3") (pinfunction "IN_3") (pintype "passive"))
      (node (ref "U8") (pin "4") (pinfunction "IN_4") (pintype "passive"))
      (node (ref "U9") (pin "3") (pinfunction "VIN_3") (pintype "passive"))
      (node (ref "U9") (pin "5") (pinfunction "EN_5") (pintype "passive"))
    )
    (net (code "74") (name "VDD") (class "Default")
      (node (ref "C2") (pin "1") (pinfunction "1_1") (pintype "passive"))
      (node (ref "C27") (pin "1") (pinfunction "1_1") (pintype "passive"))
      (node (ref "CN5") (pin "1") (pinfunction "1_1") (pintype "passive"))
      (node (ref "R18") (pin "2") (pinfunction "2_2") (pintype "passive"))
      (node (ref "R20") (pin "2") (pinfunction "2_2") (pintype "passive"))
      (node (ref "R21") (pin "2") (pinfunction "2_2") (pintype "passive"))
      (node (ref "R90") (pin "2") (pinfunction "2_2") (pintype "passive"))
      (node (ref "U1") (pin "16") (pinfunction "VCCB_16") (pintype "passive"))
      (node (ref "U10") (pin "16") (pinfunction "VCCB_16") (pintype "passive"))
    )
    (net (code "75") (name "unconnected-(CN1-RX1+-PadB11)") (class "Default")
      (node (ref "CN1") (pin "B11") (pinfunction "RX1+_B11") (pintype "passive+no_connect"))
    )
    (net (code "76") (name "unconnected-(CN1-RX1--PadB10)") (class "Default")
      (node (ref "CN1") (pin "B10") (pinfunction "RX1-_B10") (pintype "passive+no_connect"))
    )
    (net (code "77") (name "unconnected-(CN1-RX2+-PadA11)") (class "Default")
      (node (ref "CN1") (pin "A11") (pinfunction "RX2+_A11") (pintype "passive+no_connect"))
    )
    (net (code "78") (name "unconnected-(CN1-RX2--PadA10)") (class "Default")
      (node (ref "CN1") (pin "A10") (pinfunction "RX2-_A10") (pintype "passive+no_connect"))
    )
    (net (code "79") (name "unconnected-(CN1-SBU1-PadA8)") (class "Default")
      (node (ref "CN1") (pin "A8") (pinfunction "SBU1_A8") (pintype "passive+no_connect"))
    )
    (net (code "80") (name "unconnected-(CN1-SBU2-PadB8)") (class "Default")
      (node (ref "CN1") (pin "B8") (pinfunction "SBU2_B8") (pintype "passive+no_connect"))
    )
    (net (code "81") (name "unconnected-(CN1-TX1+-PadA2)") (class "Default")
      (node (ref "CN1") (pin "A2") (pinfunction "TX1+_A2") (pintype "passive+no_connect"))
    )
    (net (code "82") (name "unconnected-(CN1-TX1--PadA3)") (class "Default")
      (node (ref "CN1") (pin "A3") (pinfunction "TX1-_A3") (pintype "passive+no_connect"))
    )
    (net (code "83") (name "unconnected-(CN1-TX2+-PadB2)") (class "Default")
      (node (ref "CN1") (pin "B2") (pinfunction "TX2+_B2") (pintype "passive+no_connect"))
    )
    (net (code "84") (name "unconnected-(CN1-TX2--PadB3)") (class "Default")
      (node (ref "CN1") (pin "B3") (pinfunction "TX2-_B3") (pintype "passive+no_connect"))
    )
    (net (code "85") (name "unconnected-(CN5-Pad7)") (class "Default")
      (node (ref "CN5") (pin "7") (pinfunction "7_7") (pintype "passive+no_connect"))
    )
    (net (code "86") (name "unconnected-(U3-NC-Pad4)") (class "Default")
      (node (ref "U3") (pin "4") (pinfunction "NC_4") (pintype "passive+no_connect"))
    )
    (net (code "87") (name "unconnected-(U7A-GNDDetect{slash}PG5-PadK13)") (class "Default")
      (node (ref "U7") (pin "K13") (pinfunction "GNDDetect/PG5_K13") (pintype "passive+no_connect"))
    )
    (net (code "88") (name "unconnected-(U7A-HW_TYP_1{slash}PI5-PadC4)") (class "Default")
      (node (ref "U7") (pin "C4") (pinfunction "HW_TYP_1/PI5_C4") (pintype "passive+no_connect"))
    )
    (net (code "89") (name "unconnected-(U7A-T_JNRST{slash}PF13-PadN6)") (class "Default")
      (node (ref "U7") (pin "N6") (pinfunction "T_JNRST/PF13_N6") (pintype "passive+no_connect"))
    )
    (net (code "90") (name "unconnected-(U9-NC{slash}ADJ-Pad4)") (class "Default")
      (node (ref "U9") (pin "4") (pinfunction "NC/ADJ_4") (pintype "passive+no_connect"))
    )
  )
)
